# North_Star_Hub_Ver0_3_1.net
KiCad netlist of a schematic drawn in EAGLE
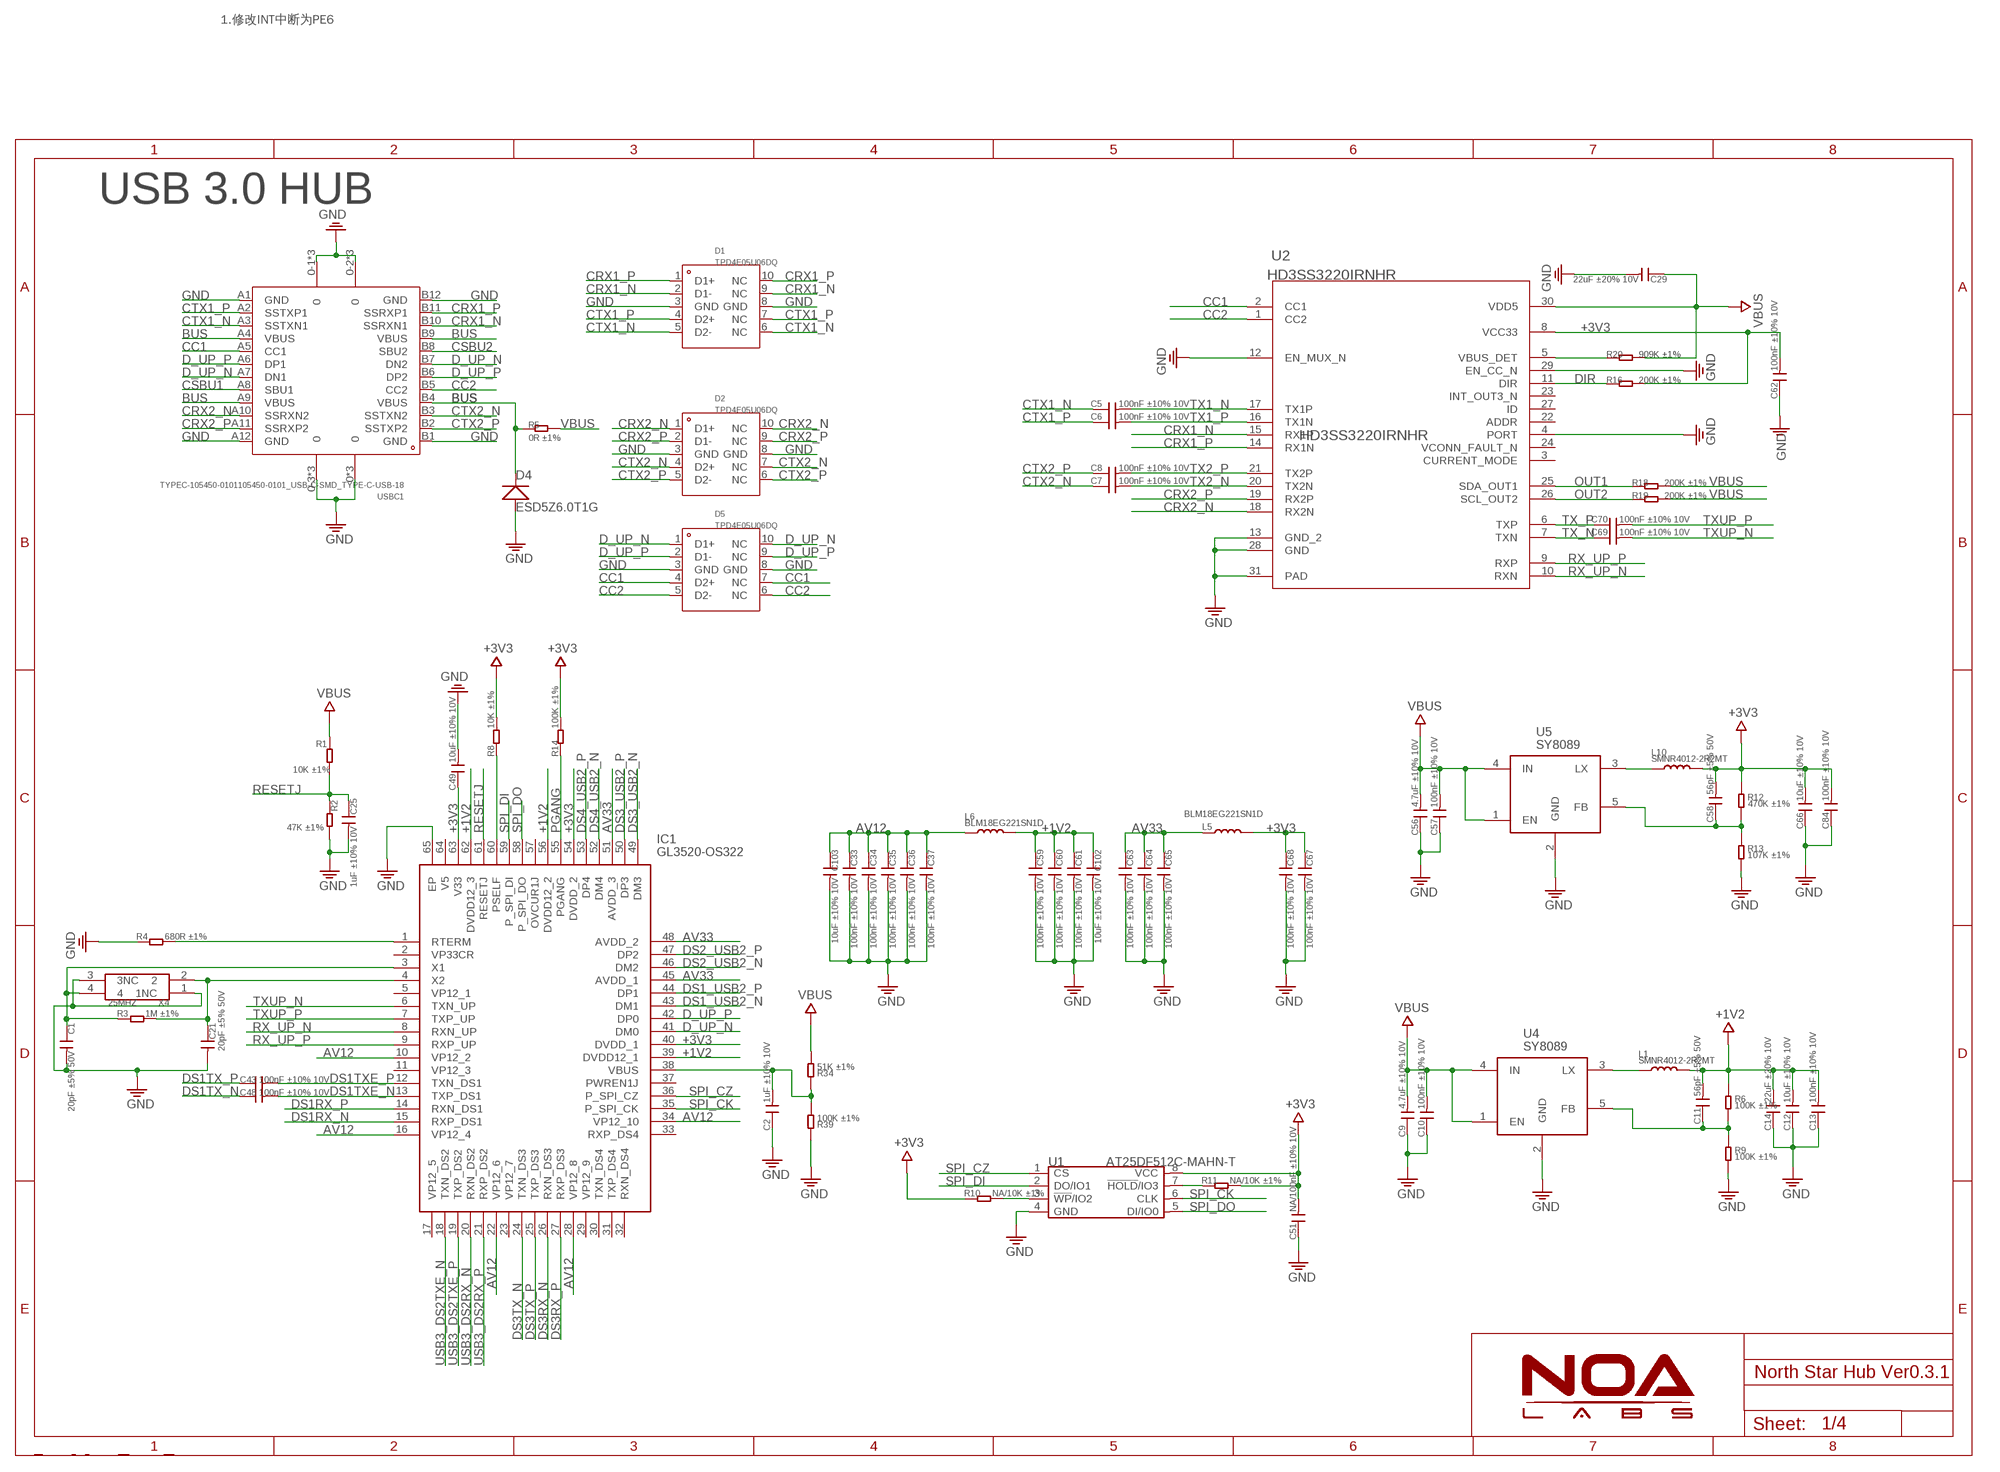
[diagram p0: schematic, sheet 1]
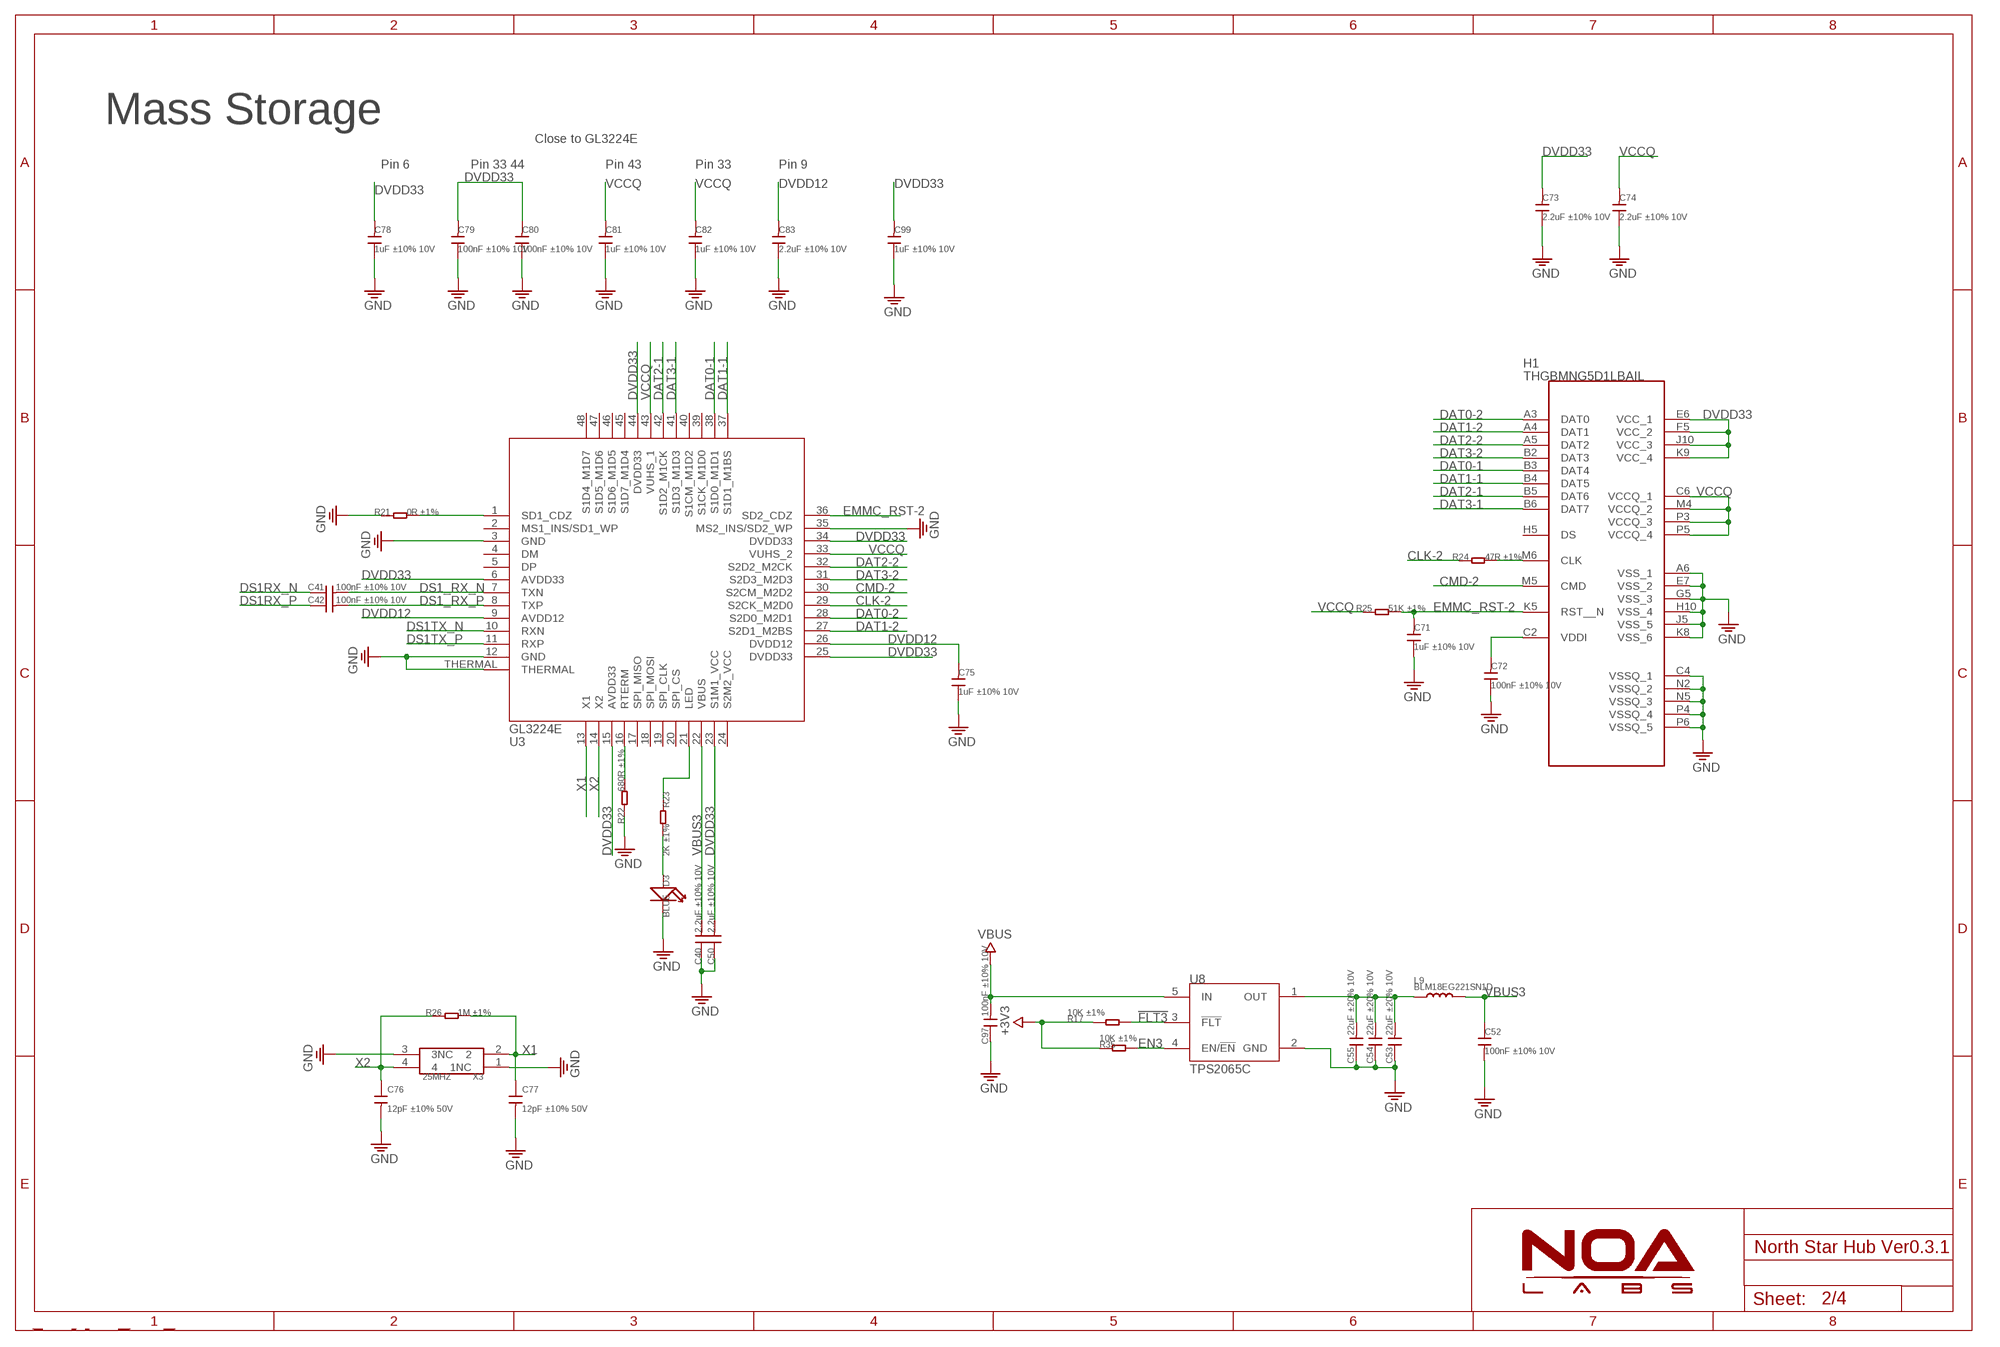
[diagram p1: schematic, sheet 2]
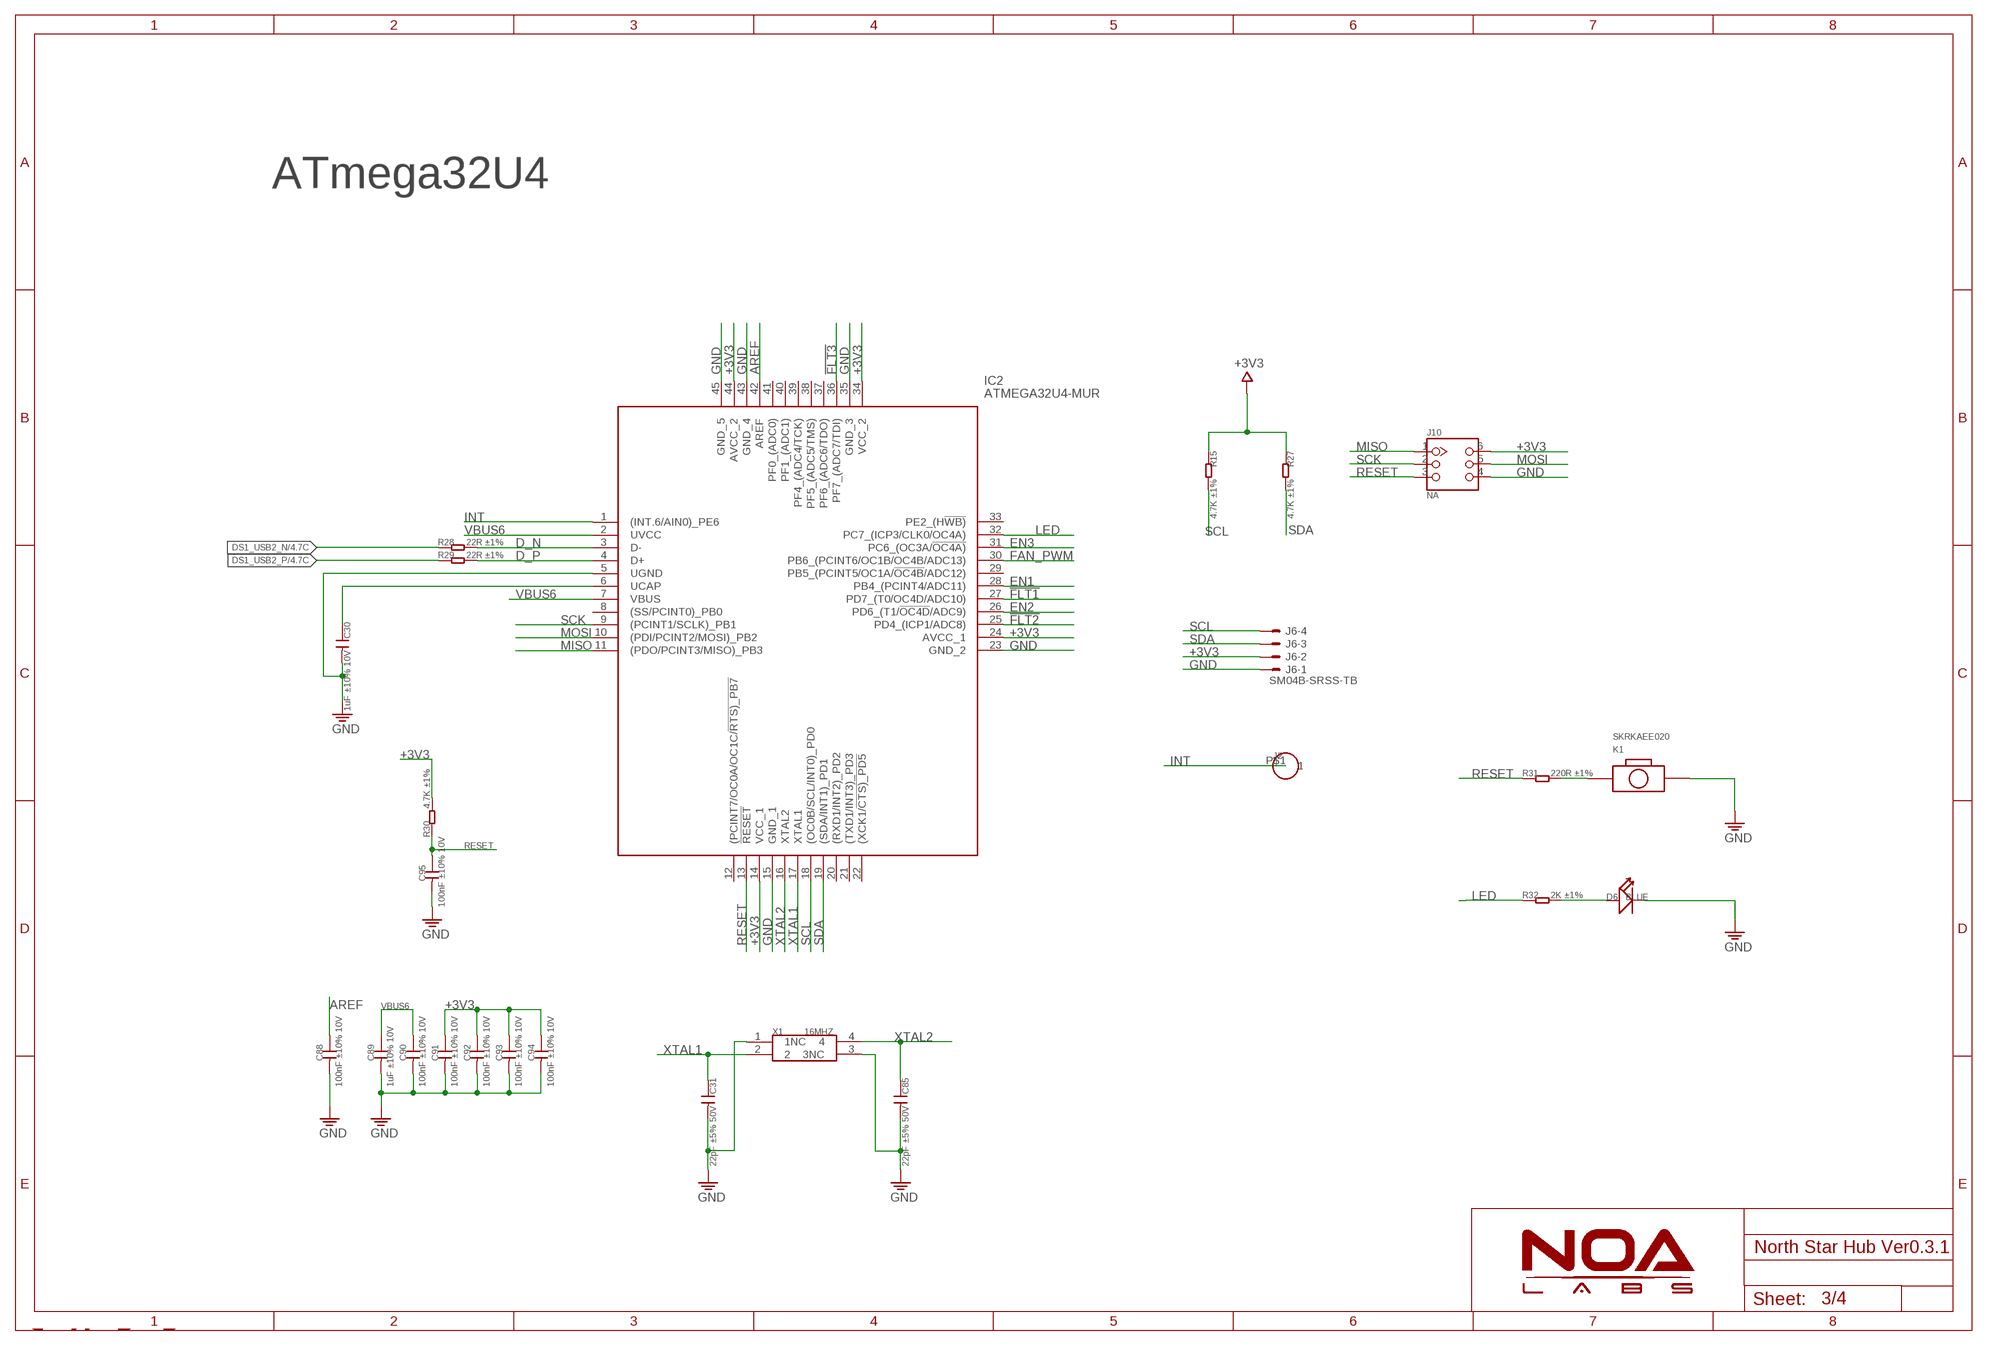
[diagram p2: schematic, sheet 3]
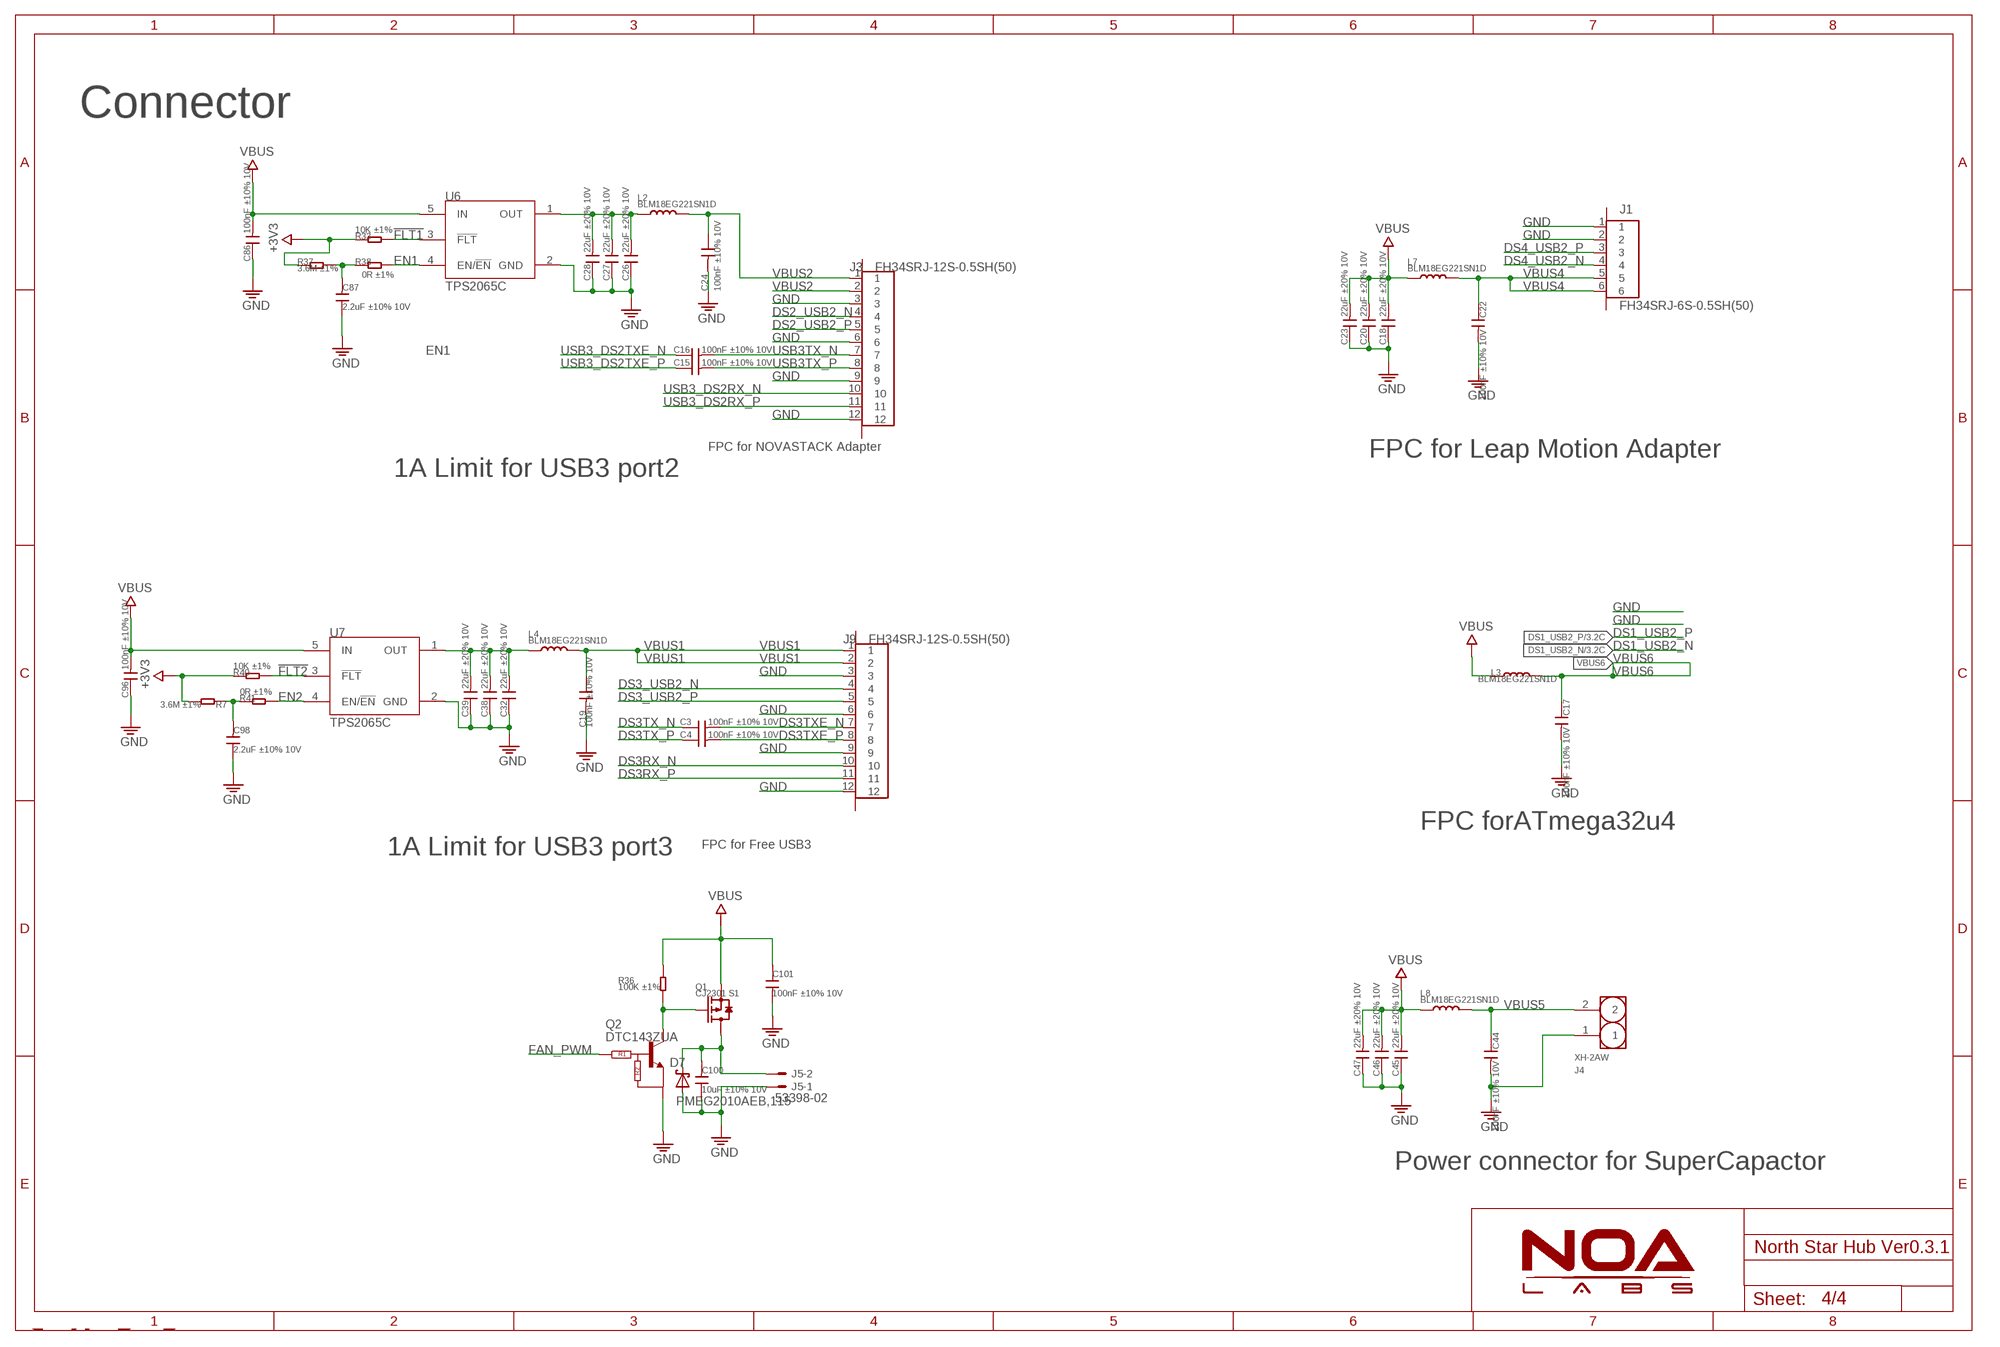
[diagram p3: schematic, sheet 4]

(export (version "E")
  (design (tool "Eeschema 10.0.6"))
  (components
    (comp (ref "C40")
      (value "2.2uF ±10% 10V")
      (footprint "eagle-import:C0402")
      (libsource (lib "eagle-import") (part "C-0402"))
    )
    (comp (ref "C41")
      (value "100nF ±10% 10V")
      (footprint "eagle-import:C0201")
      (libsource (lib "eagle-import") (part "C-0201"))
    )
    (comp (ref "C42")
      (value "100nF ±10% 10V")
      (footprint "eagle-import:C0201")
      (libsource (lib "eagle-import") (part "C-0201"))
    )
    (comp (ref "C50")
      (value "2.2uF ±10% 10V")
      (footprint "eagle-import:C0402")
      (libsource (lib "eagle-import") (part "C-0402"))
    )
    (comp (ref "C52")
      (value "100nF ±10% 10V")
      (footprint "eagle-import:C0402")
      (libsource (lib "eagle-import") (part "C-0402"))
    )
    (comp (ref "C53")
      (value "22uF ±20% 10V")
      (footprint "eagle-import:C0603")
      (libsource (lib "eagle-import") (part "C-0603"))
    )
    (comp (ref "C54")
      (value "22uF ±20% 10V")
      (footprint "eagle-import:C0603")
      (libsource (lib "eagle-import") (part "C-0603"))
    )
    (comp (ref "C55")
      (value "22uF ±20% 10V")
      (footprint "eagle-import:C0603")
      (libsource (lib "eagle-import") (part "C-0603"))
    )
    (comp (ref "C71")
      (value "1uF ±10% 10V")
      (footprint "eagle-import:C0402")
      (libsource (lib "eagle-import") (part "C-0402"))
    )
    (comp (ref "C72")
      (value "100nF ±10% 10V")
      (footprint "eagle-import:C0402")
      (libsource (lib "eagle-import") (part "C-0402"))
    )
    (comp (ref "C73")
      (value "2.2uF ±10% 10V")
      (footprint "eagle-import:C0402")
      (libsource (lib "eagle-import") (part "C-0402"))
    )
    (comp (ref "C74")
      (value "2.2uF ±10% 10V")
      (footprint "eagle-import:C0402")
      (libsource (lib "eagle-import") (part "C-0402"))
    )
    (comp (ref "C75")
      (value "1uF ±10% 10V")
      (footprint "eagle-import:C0402")
      (libsource (lib "eagle-import") (part "C-0402"))
    )
    (comp (ref "C76")
      (value "12pF ±10% 50V")
      (footprint "eagle-import:C0402")
      (libsource (lib "eagle-import") (part "C-0402"))
    )
    (comp (ref "C77")
      (value "12pF ±10% 50V")
      (footprint "eagle-import:C0402")
      (libsource (lib "eagle-import") (part "C-0402"))
    )
    (comp (ref "C78")
      (value "1uF ±10% 10V")
      (footprint "eagle-import:C0402")
      (libsource (lib "eagle-import") (part "C-0402"))
    )
    (comp (ref "C79")
      (value "100nF ±10% 10V")
      (footprint "eagle-import:C0402")
      (libsource (lib "eagle-import") (part "C-0402"))
    )
    (comp (ref "C80")
      (value "100nF ±10% 10V")
      (footprint "eagle-import:C0402")
      (libsource (lib "eagle-import") (part "C-0402"))
    )
    (comp (ref "C81")
      (value "1uF ±10% 10V")
      (footprint "eagle-import:C0402")
      (libsource (lib "eagle-import") (part "C-0402"))
    )
    (comp (ref "C82")
      (value "1uF ±10% 10V")
      (footprint "eagle-import:C0402")
      (libsource (lib "eagle-import") (part "C-0402"))
    )
    (comp (ref "C83")
      (value "2.2uF ±10% 10V")
      (footprint "eagle-import:C0402")
      (libsource (lib "eagle-import") (part "C-0402"))
    )
    (comp (ref "C97")
      (value "100nF ±10% 10V")
      (footprint "eagle-import:C0402")
      (libsource (lib "eagle-import") (part "C-0402"))
    )
    (comp (ref "C99")
      (value "1uF ±10% 10V")
      (footprint "eagle-import:C0402")
      (libsource (lib "eagle-import") (part "C-0402"))
    )
    (comp (ref "D3")
      (value "BLUE")
      (footprint "eagle-import:0402_LED")
      (libsource (lib "eagle-import") (part "LED-0402LED"))
    )
    (comp (ref "H1")
      (value "THGBMNG5D1LBAIL")
      (footprint "eagle-import:BGA153C50P14X14_11.5X13")
      (fields
        (field (name "MANUFACTURER_PART_NUMBER") "IS21ES04G-JCLI-TR")
        (field (name "MOUSER_PART_NUMBER") "870-IS21ES04GJCLITR")
      )
      (libsource (lib "eagle-import") (part "EMMC-SPECIALPAD"))
    )
    (comp (ref "L9")
      (value "BLM18EG221SN1D")
      (footprint "eagle-import:L0603")
      (libsource (lib "eagle-import") (part "L-0603"))
    )
    (comp (ref "R17")
      (value "10K ±1%")
      (footprint "eagle-import:R0402")
      (libsource (lib "eagle-import") (part "R-0402"))
    )
    (comp (ref "R21")
      (value "0R ±1%")
      (footprint "eagle-import:R0402")
      (libsource (lib "eagle-import") (part "R-0402"))
    )
    (comp (ref "R22")
      (value "680R ±1%")
      (footprint "eagle-import:R0402")
      (libsource (lib "eagle-import") (part "R-0402"))
    )
    (comp (ref "R23")
      (value "2K ±1%")
      (footprint "eagle-import:R0402")
      (libsource (lib "eagle-import") (part "R-0402"))
    )
    (comp (ref "R24")
      (value "47R ±1%")
      (footprint "eagle-import:R0402")
      (libsource (lib "eagle-import") (part "R-0402"))
    )
    (comp (ref "R25")
      (value "51K ±1%")
      (footprint "eagle-import:R0402")
      (libsource (lib "eagle-import") (part "R-0402"))
    )
    (comp (ref "R26")
      (value "1M ±1%")
      (footprint "eagle-import:R0402")
      (libsource (lib "eagle-import") (part "R-0402"))
    )
    (comp (ref "R35")
      (value "10K ±1%")
      (footprint "eagle-import:R0402")
      (libsource (lib "eagle-import") (part "R-0402"))
    )
    (comp (ref "U3")
      (value "GL3224E")
      (footprint "eagle-import:TQFN48_7MM")
      (libsource (lib "eagle-import") (part "GL3224E"))
    )
    (comp (ref "U8")
      (value "TPS2065C")
      (footprint "eagle-import:SOT23-5")
      (libsource (lib "eagle-import") (part "TPS20XXC"))
    )
    (comp (ref "X3")
      (value "25MHZ")
      (footprint "eagle-import:4P-SMD-2X1.6MM")
      (libsource (lib "eagle-import") (part "CRYSTAL-XTAL-4P"))
    )
    (comp (ref "C1")
      (value "20pF ±5% 50V")
      (footprint "eagle-import:C0402")
      (libsource (lib "eagle-import") (part "C-0402"))
    )
    (comp (ref "C2")
      (value "1uF ±10% 10V")
      (footprint "eagle-import:C0402")
      (libsource (lib "eagle-import") (part "C-0402"))
    )
    (comp (ref "C5")
      (value "100nF ±10% 10V")
      (footprint "eagle-import:C0201")
      (libsource (lib "eagle-import") (part "C-0201"))
    )
    (comp (ref "C6")
      (value "100nF ±10% 10V")
      (footprint "eagle-import:C0201")
      (libsource (lib "eagle-import") (part "C-0201"))
    )
    (comp (ref "C7")
      (value "100nF ±10% 10V")
      (footprint "eagle-import:C0201")
      (libsource (lib "eagle-import") (part "C-0201"))
    )
    (comp (ref "C8")
      (value "100nF ±10% 10V")
      (footprint "eagle-import:C0201")
      (libsource (lib "eagle-import") (part "C-0201"))
    )
    (comp (ref "C9")
      (value "4.7uF ±10% 10V")
      (footprint "eagle-import:C0603")
      (libsource (lib "eagle-import") (part "C-0603"))
    )
    (comp (ref "C10")
      (value "100nF ±10% 10V")
      (footprint "eagle-import:C0402")
      (libsource (lib "eagle-import") (part "C-0402"))
    )
    (comp (ref "C11")
      (value "56pF ±5% 50V")
      (footprint "eagle-import:C0402")
      (libsource (lib "eagle-import") (part "C-0402"))
    )
    (comp (ref "C12")
      (value "10uF ±10% 10V")
      (footprint "eagle-import:C0603")
      (libsource (lib "eagle-import") (part "C-0603"))
    )
    (comp (ref "C13")
      (value "100nF ±10% 10V")
      (footprint "eagle-import:C0402")
      (libsource (lib "eagle-import") (part "C-0402"))
    )
    (comp (ref "C14")
      (value "22uF ±20% 10V")
      (footprint "eagle-import:C0805")
      (libsource (lib "eagle-import") (part "C-0805"))
    )
    (comp (ref "C21")
      (value "20pF ±5% 50V")
      (footprint "eagle-import:C0402")
      (libsource (lib "eagle-import") (part "C-0402"))
    )
    (comp (ref "C25")
      (value "1uF ±10% 10V")
      (footprint "eagle-import:C0402")
      (libsource (lib "eagle-import") (part "C-0402"))
    )
    (comp (ref "C29")
      (value "22uF ±20% 10V")
      (footprint "eagle-import:C0805")
      (libsource (lib "eagle-import") (part "C-0805"))
    )
    (comp (ref "C33")
      (value "100nF ±10% 10V")
      (footprint "eagle-import:C0402")
      (libsource (lib "eagle-import") (part "C-0402"))
    )
    (comp (ref "C34")
      (value "100nF ±10% 10V")
      (footprint "eagle-import:C0402")
      (libsource (lib "eagle-import") (part "C-0402"))
    )
    (comp (ref "C35")
      (value "100nF ±10% 10V")
      (footprint "eagle-import:C0402")
      (libsource (lib "eagle-import") (part "C-0402"))
    )
    (comp (ref "C36")
      (value "100nF ±10% 10V")
      (footprint "eagle-import:C0402")
      (libsource (lib "eagle-import") (part "C-0402"))
    )
    (comp (ref "C37")
      (value "100nF ±10% 10V")
      (footprint "eagle-import:C0402")
      (libsource (lib "eagle-import") (part "C-0402"))
    )
    (comp (ref "C43")
      (value "100nF ±10% 10V")
      (footprint "eagle-import:C0201")
      (libsource (lib "eagle-import") (part "C-0201"))
    )
    (comp (ref "C48")
      (value "100nF ±10% 10V")
      (footprint "eagle-import:C0201")
      (libsource (lib "eagle-import") (part "C-0201"))
    )
    (comp (ref "C49")
      (value "10uF ±10% 10V")
      (footprint "eagle-import:C0603")
      (libsource (lib "eagle-import") (part "C-0603"))
    )
    (comp (ref "C51")
      (value "NA/100nF ±10% 10V")
      (footprint "eagle-import:C0402")
      (libsource (lib "eagle-import") (part "C-0402"))
    )
    (comp (ref "C56")
      (value "4.7uF ±10% 10V")
      (footprint "eagle-import:C0603")
      (libsource (lib "eagle-import") (part "C-0603"))
    )
    (comp (ref "C57")
      (value "100nF ±10% 10V")
      (footprint "eagle-import:C0402")
      (libsource (lib "eagle-import") (part "C-0402"))
    )
    (comp (ref "C58")
      (value "56pF ±5% 50V")
      (footprint "eagle-import:C0402")
      (libsource (lib "eagle-import") (part "C-0402"))
    )
    (comp (ref "C59")
      (value "100nF ±10% 10V")
      (footprint "eagle-import:C0402")
      (libsource (lib "eagle-import") (part "C-0402"))
    )
    (comp (ref "C60")
      (value "100nF ±10% 10V")
      (footprint "eagle-import:C0402")
      (libsource (lib "eagle-import") (part "C-0402"))
    )
    (comp (ref "C61")
      (value "100nF ±10% 10V")
      (footprint "eagle-import:C0402")
      (libsource (lib "eagle-import") (part "C-0402"))
    )
    (comp (ref "C62")
      (value "100nF ±10% 10V")
      (footprint "eagle-import:C0402")
      (libsource (lib "eagle-import") (part "C-0402"))
    )
    (comp (ref "C63")
      (value "100nF ±10% 10V")
      (footprint "eagle-import:C0402")
      (libsource (lib "eagle-import") (part "C-0402"))
    )
    (comp (ref "C64")
      (value "100nF ±10% 10V")
      (footprint "eagle-import:C0402")
      (libsource (lib "eagle-import") (part "C-0402"))
    )
    (comp (ref "C65")
      (value "100nF ±10% 10V")
      (footprint "eagle-import:C0402")
      (libsource (lib "eagle-import") (part "C-0402"))
    )
    (comp (ref "C66")
      (value "10uF ±10% 10V")
      (footprint "eagle-import:C0603")
      (libsource (lib "eagle-import") (part "C-0603"))
    )
    (comp (ref "C67")
      (value "100nF ±10% 10V")
      (footprint "eagle-import:C0402")
      (libsource (lib "eagle-import") (part "C-0402"))
    )
    (comp (ref "C68")
      (value "100nF ±10% 10V")
      (footprint "eagle-import:C0402")
      (libsource (lib "eagle-import") (part "C-0402"))
    )
    (comp (ref "C69")
      (value "100nF ±10% 10V")
      (footprint "eagle-import:C0201")
      (libsource (lib "eagle-import") (part "C-0201"))
    )
    (comp (ref "C70")
      (value "100nF ±10% 10V")
      (footprint "eagle-import:C0201")
      (libsource (lib "eagle-import") (part "C-0201"))
    )
    (comp (ref "C84")
      (value "100nF ±10% 10V")
      (footprint "eagle-import:C0402")
      (libsource (lib "eagle-import") (part "C-0402"))
    )
    (comp (ref "C102")
      (value "10uF ±10% 10V")
      (footprint "eagle-import:C0603")
      (libsource (lib "eagle-import") (part "C-0603"))
    )
    (comp (ref "C103")
      (value "10uF ±10% 10V")
      (footprint "eagle-import:C0603")
      (libsource (lib "eagle-import") (part "C-0603"))
    )
    (comp (ref "D1")
      (value "TPD4E05U06DQ")
      (footprint "eagle-import:USON-10_L2.5-W1.0-P0.50-BL")
      (fields
        (field (name "BOM_MANUFACTURER_PART") "TPD4E05U06DQAR")
        (field (name "BOM_SUPPLIER_PART") "C138714")
        (field (name "CONTRIBUTOR") "LCSC")
      )
      (libsource (lib "eagle-import") (part "TPD4E05U06DQARTPD4E05U06DQAR_C138714_USON-10_L2.5-W1.0-P0.50-BL"))
    )
    (comp (ref "D2")
      (value "TPD4E05U06DQ")
      (footprint "eagle-import:USON-10_L2.5-W1.0-P0.50-BL")
      (fields
        (field (name "BOM_MANUFACTURER_PART") "TPD4E05U06DQAR")
        (field (name "BOM_SUPPLIER_PART") "C138714")
        (field (name "CONTRIBUTOR") "LCSC")
      )
      (libsource (lib "eagle-import") (part "TPD4E05U06DQARTPD4E05U06DQAR_C138714_USON-10_L2.5-W1.0-P0.50-BL"))
    )
    (comp (ref "D4")
      (value "ESD5Z6.0T1G")
      (footprint "eagle-import:SOD523")
      (libsource (lib "eagle-import") (part "D-0603"))
    )
    (comp (ref "D5")
      (value "TPD4E05U06DQ")
      (footprint "eagle-import:USON-10_L2.5-W1.0-P0.50-BL")
      (fields
        (field (name "BOM_MANUFACTURER_PART") "TPD4E05U06DQAR")
        (field (name "BOM_SUPPLIER_PART") "C138714")
        (field (name "CONTRIBUTOR") "LCSC")
      )
      (libsource (lib "eagle-import") (part "TPD4E05U06DQARTPD4E05U06DQAR_C138714_USON-10_L2.5-W1.0-P0.50-BL"))
    )
    (comp (ref "IC1")
      (value "GL3520-OS322")
      (footprint "eagle-import:QFN40P800X800X80-65N")
      (fields (field (name "MANUFACTURER_PART_NUMBER") "GL3520 64"))
      (libsource (lib "eagle-import") (part "GL3520_64"))
    )
    (comp (ref "L1")
      (value "SMNR4012-2R2MT")
      (footprint "eagle-import:L4012")
      (libsource (lib "eagle-import") (part "L-4012"))
    )
    (comp (ref "L5")
      (value "BLM18EG221SN1D")
      (footprint "eagle-import:L0603")
      (libsource (lib "eagle-import") (part "L-0603"))
    )
    (comp (ref "L6")
      (value "BLM18EG221SN1D")
      (footprint "eagle-import:L0603")
      (libsource (lib "eagle-import") (part "L-0603"))
    )
    (comp (ref "L10")
      (value "SMNR4012-2R2MT")
      (footprint "eagle-import:L4012")
      (libsource (lib "eagle-import") (part "L-4012"))
    )
    (comp (ref "R1")
      (value "10K ±1%")
      (footprint "eagle-import:R0402")
      (libsource (lib "eagle-import") (part "R-0402"))
    )
    (comp (ref "R2")
      (value "47K ±1%")
      (footprint "eagle-import:R0402")
      (libsource (lib "eagle-import") (part "R-0402"))
    )
    (comp (ref "R3")
      (value "1M ±1%")
      (footprint "eagle-import:R0402")
      (libsource (lib "eagle-import") (part "R-0402"))
    )
    (comp (ref "R4")
      (value "680R ±1%")
      (footprint "eagle-import:R0402")
      (libsource (lib "eagle-import") (part "R-0402"))
    )
    (comp (ref "R5")
      (value "0R ±1%")
      (footprint "eagle-import:R0805")
      (libsource (lib "eagle-import") (part "R-0805"))
    )
    (comp (ref "R6")
      (value "100K ±1%")
      (footprint "eagle-import:R0402")
      (libsource (lib "eagle-import") (part "R-0402"))
    )
    (comp (ref "R8")
      (value "10K ±1%")
      (footprint "eagle-import:R0402")
      (libsource (lib "eagle-import") (part "R-0402"))
    )
    (comp (ref "R9")
      (value "100K ±1%")
      (footprint "eagle-import:R0402")
      (libsource (lib "eagle-import") (part "R-0402"))
    )
    (comp (ref "R10")
      (value "NA/10K ±1%")
      (footprint "eagle-import:R0402")
      (libsource (lib "eagle-import") (part "R-0402"))
    )
    (comp (ref "R11")
      (value "NA/10K ±1%")
      (footprint "eagle-import:R0402")
      (libsource (lib "eagle-import") (part "R-0402"))
    )
    (comp (ref "R12")
      (value "470K ±1%")
      (footprint "eagle-import:R0402")
      (libsource (lib "eagle-import") (part "R-0402"))
    )
    (comp (ref "R13")
      (value "107K ±1%")
      (footprint "eagle-import:R0402")
      (libsource (lib "eagle-import") (part "R-0402"))
    )
    (comp (ref "R14")
      (value "100K ±1%")
      (footprint "eagle-import:R0402")
      (libsource (lib "eagle-import") (part "R-0402"))
    )
    (comp (ref "R16")
      (value "200K ±1%")
      (footprint "eagle-import:R0402")
      (libsource (lib "eagle-import") (part "R-0402"))
    )
    (comp (ref "R18")
      (value "200K ±1%")
      (footprint "eagle-import:R0402")
      (libsource (lib "eagle-import") (part "R-0402"))
    )
    (comp (ref "R19")
      (value "200K ±1%")
      (footprint "eagle-import:R0402")
      (libsource (lib "eagle-import") (part "R-0402"))
    )
    (comp (ref "R20")
      (value "909K ±1%")
      (footprint "eagle-import:R0402")
      (libsource (lib "eagle-import") (part "R-0402"))
    )
    (comp (ref "R34")
      (value "51K ±1%")
      (footprint "eagle-import:R0402")
      (libsource (lib "eagle-import") (part "R-0402"))
    )
    (comp (ref "R39")
      (value "100K ±1%")
      (footprint "eagle-import:R0402")
      (libsource (lib "eagle-import") (part "R-0402"))
    )
    (comp (ref "U1")
      (value "AT25DF512C-MAHN-T")
      (footprint "eagle-import:SOIC8-6.0")
      (libsource (lib "eagle-import") (part "W25Q"))
    )
    (comp (ref "U2")
      (value "HD3SS3220IRNHR")
      (footprint "eagle-import:RNH0030A")
      (fields (field (name "MANUFACTURER") "Texas Instruments"))
      (libsource (lib "eagle-import") (part "HD3SS3220IRNHR"))
    )
    (comp (ref "U4")
      (value "SY8089")
      (footprint "eagle-import:SOT23-5")
      (libsource (lib "eagle-import") (part "SY8089"))
    )
    (comp (ref "U5")
      (value "SY8089")
      (footprint "eagle-import:SOT23-5")
      (libsource (lib "eagle-import") (part "SY8089"))
    )
    (comp (ref "USBC1")
      (value "TYPEC-105450-0101105450-0101_USB-C-SMD_TYPE-C-USB-18")
      (footprint "eagle-import:USB-C-SMD_TYPE-C-USB-18")
      (fields
        (field (name "BOM_MANUFACTURER_PART") "105450-0101")
        (field (name "BOM_SUPPLIER_PART") "C134092")
        (field (name "CONTRIBUTOR") "LCSC")
      )
      (libsource (lib "eagle-import") (part "TYPEC-105450-0101105450-0101_USB-C-SMD_TYPE-C-USB-18"))
    )
    (comp (ref "X4")
      (value "25MHZ")
      (footprint "eagle-import:4P-SMD-2X1.6MM")
      (libsource (lib "eagle-import") (part "CRYSTAL-XTAL-4P"))
    )
    (comp (ref "C3")
      (value "100nF ±10% 10V")
      (footprint "eagle-import:C0201")
      (libsource (lib "eagle-import") (part "C-0201"))
    )
    (comp (ref "C4")
      (value "100nF ±10% 10V")
      (footprint "eagle-import:C0201")
      (libsource (lib "eagle-import") (part "C-0201"))
    )
    (comp (ref "C15")
      (value "100nF ±10% 10V")
      (footprint "eagle-import:C0201")
      (libsource (lib "eagle-import") (part "C-0201"))
    )
    (comp (ref "C16")
      (value "100nF ±10% 10V")
      (footprint "eagle-import:C0201")
      (libsource (lib "eagle-import") (part "C-0201"))
    )
    (comp (ref "C17")
      (value "100nF ±10% 10V")
      (footprint "eagle-import:C0402")
      (libsource (lib "eagle-import") (part "C-0402"))
    )
    (comp (ref "C18")
      (value "22uF ±20% 10V")
      (footprint "eagle-import:C0603")
      (libsource (lib "eagle-import") (part "C-0603"))
    )
    (comp (ref "C19")
      (value "100nF ±10% 10V")
      (footprint "eagle-import:C0402")
      (libsource (lib "eagle-import") (part "C-0402"))
    )
    (comp (ref "C20")
      (value "22uF ±20% 10V")
      (footprint "eagle-import:C0603")
      (libsource (lib "eagle-import") (part "C-0603"))
    )
    (comp (ref "C22")
      (value "100nF ±10% 10V")
      (footprint "eagle-import:C0402")
      (libsource (lib "eagle-import") (part "C-0402"))
    )
    (comp (ref "C23")
      (value "22uF ±20% 10V")
      (footprint "eagle-import:C0603")
      (libsource (lib "eagle-import") (part "C-0603"))
    )
    (comp (ref "C24")
      (value "100nF ±10% 10V")
      (footprint "eagle-import:C0402")
      (libsource (lib "eagle-import") (part "C-0402"))
    )
    (comp (ref "C26")
      (value "22uF ±20% 10V")
      (footprint "eagle-import:C0603")
      (libsource (lib "eagle-import") (part "C-0603"))
    )
    (comp (ref "C27")
      (value "22uF ±20% 10V")
      (footprint "eagle-import:C0603")
      (libsource (lib "eagle-import") (part "C-0603"))
    )
    (comp (ref "C28")
      (value "22uF ±20% 10V")
      (footprint "eagle-import:C0603")
      (libsource (lib "eagle-import") (part "C-0603"))
    )
    (comp (ref "C32")
      (value "22uF ±20% 10V")
      (footprint "eagle-import:C0603")
      (libsource (lib "eagle-import") (part "C-0603"))
    )
    (comp (ref "C38")
      (value "22uF ±20% 10V")
      (footprint "eagle-import:C0603")
      (libsource (lib "eagle-import") (part "C-0603"))
    )
    (comp (ref "C39")
      (value "22uF ±20% 10V")
      (footprint "eagle-import:C0603")
      (libsource (lib "eagle-import") (part "C-0603"))
    )
    (comp (ref "C44")
      (value "100nF ±10% 10V")
      (footprint "eagle-import:C0402")
      (libsource (lib "eagle-import") (part "C-0402"))
    )
    (comp (ref "C45")
      (value "22uF ±20% 10V")
      (footprint "eagle-import:C0603")
      (libsource (lib "eagle-import") (part "C-0603"))
    )
    (comp (ref "C46")
      (value "22uF ±20% 10V")
      (footprint "eagle-import:C0603")
      (libsource (lib "eagle-import") (part "C-0603"))
    )
    (comp (ref "C47")
      (value "22uF ±20% 10V")
      (footprint "eagle-import:C0603")
      (libsource (lib "eagle-import") (part "C-0603"))
    )
    (comp (ref "C86")
      (value "100nF ±10% 10V")
      (footprint "eagle-import:C0402")
      (libsource (lib "eagle-import") (part "C-0402"))
    )
    (comp (ref "C87")
      (value "2.2uF ±10% 10V")
      (footprint "eagle-import:C0402")
      (libsource (lib "eagle-import") (part "C-0402"))
    )
    (comp (ref "C96")
      (value "100nF ±10% 10V")
      (footprint "eagle-import:C0402")
      (libsource (lib "eagle-import") (part "C-0402"))
    )
    (comp (ref "C98")
      (value "2.2uF ±10% 10V")
      (footprint "eagle-import:C0402")
      (libsource (lib "eagle-import") (part "C-0402"))
    )
    (comp (ref "C100")
      (value "10uF ±10% 10V")
      (footprint "eagle-import:C0603")
      (libsource (lib "eagle-import") (part "C-0603"))
    )
    (comp (ref "C101")
      (value "100nF ±10% 10V")
      (footprint "eagle-import:C0402")
      (libsource (lib "eagle-import") (part "C-0402"))
    )
    (comp (ref "D7")
      (value "PMEG2010AEB,115")
      (footprint "eagle-import:SOD323")
      (libsource (lib "eagle-import") (part "SCHOTTKY-SOD323"))
    )
    (comp (ref "J1")
      (value "FH34SRJ-6S-0.5SH(50)")
      (footprint "eagle-import:FH34RJ-6S")
      (libsource (lib "eagle-import") (part "FPC-0.5-6P-FH34RJ"))
    )
    (comp (ref "J3")
      (value "FH34SRJ-12S-0.5SH(50)")
      (footprint "eagle-import:FPC-0.5-12P")
      (libsource (lib "eagle-import") (part "FPC-0.5-12PFPC-0.5-12P"))
    )
    (comp (ref "J4")
      (value "XH-2AW")
      (footprint "eagle-import:XH-02-90")
      (libsource (lib "eagle-import") (part "HEADER-2P-90DEG-FEMALE"))
    )
    (comp (ref "J5")
      (value "53398-02")
      (footprint "eagle-import:53398-02")
      (fields (field (name "MF") "MOLEX"))
      (libsource (lib "eagle-import") (part "53?-02398"))
    )
    (comp (ref "J9")
      (value "FH34SRJ-12S-0.5SH(50)")
      (footprint "eagle-import:FPC-0.5-12P")
      (libsource (lib "eagle-import") (part "FPC-0.5-12PFPC-0.5-12P"))
    )
    (comp (ref "L2")
      (value "BLM18EG221SN1D")
      (footprint "eagle-import:L0603")
      (libsource (lib "eagle-import") (part "L-0603"))
    )
    (comp (ref "L3")
      (value "BLM18EG221SN1D")
      (footprint "eagle-import:L0603")
      (libsource (lib "eagle-import") (part "L-0603"))
    )
    (comp (ref "L4")
      (value "BLM18EG221SN1D")
      (footprint "eagle-import:L0603")
      (libsource (lib "eagle-import") (part "L-0603"))
    )
    (comp (ref "L7")
      (value "BLM18EG221SN1D")
      (footprint "eagle-import:L0603")
      (libsource (lib "eagle-import") (part "L-0603"))
    )
    (comp (ref "L8")
      (value "BLM18EG221SN1D")
      (footprint "eagle-import:L0603")
      (libsource (lib "eagle-import") (part "L-0603"))
    )
    (comp (ref "Q1")
      (value "CJ2301 S1")
      (footprint "eagle-import:SOT23")
      (libsource (lib "eagle-import") (part "MOSFET-P-SOT23"))
    )
    (comp (ref "Q2")
      (value "DTC143ZUA")
      (footprint "eagle-import:SOT323")
      (libsource (lib "eagle-import") (part "DIGITAL-NPNUE"))
    )
    (comp (ref "R7")
      (value "3.6M ±1%")
      (footprint "eagle-import:R0402")
      (libsource (lib "eagle-import") (part "R-0402"))
    )
    (comp (ref "R33")
      (value "10K ±1%")
      (footprint "eagle-import:R0402")
      (libsource (lib "eagle-import") (part "R-0402"))
    )
    (comp (ref "R36")
      (value "100K ±1%")
      (footprint "eagle-import:R0402")
      (libsource (lib "eagle-import") (part "R-0402"))
    )
    (comp (ref "R37")
      (value "3.6M ±1%")
      (footprint "eagle-import:R0402")
      (libsource (lib "eagle-import") (part "R-0402"))
    )
    (comp (ref "R38")
      (value "0R ±1%")
      (footprint "eagle-import:R0402")
      (libsource (lib "eagle-import") (part "R-0402"))
    )
    (comp (ref "R40")
      (value "10K ±1%")
      (footprint "eagle-import:R0402")
      (libsource (lib "eagle-import") (part "R-0402"))
    )
    (comp (ref "R41")
      (value "0R ±1%")
      (footprint "eagle-import:R0402")
      (libsource (lib "eagle-import") (part "R-0402"))
    )
    (comp (ref "U6")
      (value "TPS2065C")
      (footprint "eagle-import:SOT23-5")
      (libsource (lib "eagle-import") (part "TPS20XXC"))
    )
    (comp (ref "U7")
      (value "TPS2065C")
      (footprint "eagle-import:SOT23-5")
      (libsource (lib "eagle-import") (part "TPS20XXC"))
    )
    (comp (ref "C30")
      (value "1uF ±10% 10V")
      (footprint "eagle-import:C0402")
      (libsource (lib "eagle-import") (part "C-0402"))
    )
    (comp (ref "C31")
      (value "22pF ±5% 50V")
      (footprint "eagle-import:C0402")
      (libsource (lib "eagle-import") (part "C-0402"))
    )
    (comp (ref "C85")
      (value "22pF ±5% 50V")
      (footprint "eagle-import:C0402")
      (libsource (lib "eagle-import") (part "C-0402"))
    )
    (comp (ref "C88")
      (value "100nF ±10% 10V")
      (footprint "eagle-import:C0402")
      (libsource (lib "eagle-import") (part "C-0402"))
    )
    (comp (ref "C89")
      (value "1uF ±10% 10V")
      (footprint "eagle-import:C0402")
      (libsource (lib "eagle-import") (part "C-0402"))
    )
    (comp (ref "C90")
      (value "100nF ±10% 10V")
      (footprint "eagle-import:C0402")
      (libsource (lib "eagle-import") (part "C-0402"))
    )
    (comp (ref "C91")
      (value "100nF ±10% 10V")
      (footprint "eagle-import:C0402")
      (libsource (lib "eagle-import") (part "C-0402"))
    )
    (comp (ref "C92")
      (value "100nF ±10% 10V")
      (footprint "eagle-import:C0402")
      (libsource (lib "eagle-import") (part "C-0402"))
    )
    (comp (ref "C93")
      (value "100nF ±10% 10V")
      (footprint "eagle-import:C0402")
      (libsource (lib "eagle-import") (part "C-0402"))
    )
    (comp (ref "C94")
      (value "100nF ±10% 10V")
      (footprint "eagle-import:C0402")
      (libsource (lib "eagle-import") (part "C-0402"))
    )
    (comp (ref "C95")
      (value "100nF ±10% 10V")
      (footprint "eagle-import:C0402")
      (libsource (lib "eagle-import") (part "C-0402"))
    )
    (comp (ref "D6")
      (value "BLUE")
      (footprint "eagle-import:0402_LED")
      (libsource (lib "eagle-import") (part "LED-0402LED"))
    )
    (comp (ref "IC2")
      (value "ATMEGA32U4-MUR")
      (footprint "eagle-import:QFN50P700X700X100-45N")
      (fields
        (field (name "MANUFACTURER_PART_NUMBER") "ATMEGA32U4-MU")
        (field (name "MOUSER_PART_NUMBER") "556-ATMEGA32U4-MU")
        (field (name "RS_PART_NUMBER") "1310290P")
      )
      (libsource (lib "eagle-import") (part "ATMEGA32U4-MU"))
    )
    (comp (ref "J2")
      (value "HEADER-1P-32")
      (footprint "eagle-import:1P-60_32MIL")
      (libsource (lib "eagle-import") (part "HEADER-1P-32"))
    )
    (comp (ref "J6")
      (value "SM04B-SRSS-TB")
      (footprint "eagle-import:SM04B-SRSS-TB")
      (libsource (lib "eagle-import") (part "?M04B-SRSS-TBS"))
    )
    (comp (ref "J10")
      (value "NA")
      (footprint "eagle-import:2X3P-2.54-65_35MIL")
      (libsource (lib "eagle-import") (part "HEADER-2X3P-THT"))
    )
    (comp (ref "K1")
      (value "SKRKAEE020")
      (footprint "eagle-import:SKRKAEE020")
      (libsource (lib "eagle-import") (part "BUTTON-2PSKRKAEE020"))
    )
    (comp (ref "R15")
      (value "4.7K ±1%")
      (footprint "eagle-import:R0402")
      (libsource (lib "eagle-import") (part "R-0402"))
    )
    (comp (ref "R27")
      (value "4.7K ±1%")
      (footprint "eagle-import:R0402")
      (libsource (lib "eagle-import") (part "R-0402"))
    )
    (comp (ref "R28")
      (value "22R ±1%")
      (footprint "eagle-import:R0402")
      (libsource (lib "eagle-import") (part "R-0402"))
    )
    (comp (ref "R29")
      (value "22R ±1%")
      (footprint "eagle-import:R0402")
      (libsource (lib "eagle-import") (part "R-0402"))
    )
    (comp (ref "R30")
      (value "4.7K ±1%")
      (footprint "eagle-import:R0402")
      (libsource (lib "eagle-import") (part "R-0402"))
    )
    (comp (ref "R31")
      (value "220R ±1%")
      (footprint "eagle-import:R0402")
      (libsource (lib "eagle-import") (part "R-0402"))
    )
    (comp (ref "R32")
      (value "2K ±1%")
      (footprint "eagle-import:R0402")
      (libsource (lib "eagle-import") (part "R-0402"))
    )
    (comp (ref "X1")
      (value "16MHZ")
      (footprint "eagle-import:4P-SMD-3.2X2.5")
      (libsource (lib "eagle-import") (part "CRYSTAL-XTAL-4P-3225"))
    )
  )
  (nets
    (net (code "1") (name "+1V2") (class "Default")
      (node (ref "C102") (pin "1") (pinfunction "1_1") (pintype "passive"))
      (node (ref "C11") (pin "2") (pinfunction "2_2") (pintype "passive"))
      (node (ref "C12") (pin "2") (pinfunction "2_2") (pintype "passive"))
      (node (ref "C13") (pin "2") (pinfunction "2_2") (pintype "passive"))
      (node (ref "C14") (pin "2") (pinfunction "2_2") (pintype "passive"))
      (node (ref "C59") (pin "1") (pinfunction "1_1") (pintype "passive"))
      (node (ref "C60") (pin "1") (pinfunction "1_1") (pintype "passive"))
      (node (ref "C61") (pin "1") (pinfunction "1_1") (pintype "passive"))
      (node (ref "IC1") (pin "39") (pinfunction "DVDD12_1_39") (pintype "bidirectional"))
      (node (ref "IC1") (pin "56") (pinfunction "DVDD12_2_56") (pintype "bidirectional"))
      (node (ref "IC1") (pin "62") (pinfunction "DVDD12_3_62") (pintype "bidirectional"))
      (node (ref "L1") (pin "2") (pinfunction "2_2") (pintype "passive"))
      (node (ref "L6") (pin "2") (pinfunction "2_2") (pintype "passive"))
      (node (ref "R6") (pin "1") (pinfunction "1_1") (pintype "passive"))
    )
    (net (code "2") (name "+3V3") (class "Default")
      (node (ref "C49") (pin "1") (pinfunction "1_1") (pintype "passive"))
      (node (ref "C51") (pin "2") (pinfunction "2_2") (pintype "passive"))
      (node (ref "C58") (pin "2") (pinfunction "2_2") (pintype "passive"))
      (node (ref "C62") (pin "2") (pinfunction "2_2") (pintype "passive"))
      (node (ref "C66") (pin "2") (pinfunction "2_2") (pintype "passive"))
      (node (ref "C67") (pin "1") (pinfunction "1_1") (pintype "passive"))
      (node (ref "C68") (pin "1") (pinfunction "1_1") (pintype "passive"))
      (node (ref "C84") (pin "2") (pinfunction "2_2") (pintype "passive"))
      (node (ref "C91") (pin "1") (pinfunction "1_1") (pintype "passive"))
      (node (ref "C92") (pin "1") (pinfunction "1_1") (pintype "passive"))
      (node (ref "C93") (pin "1") (pinfunction "1_1") (pintype "passive"))
      (node (ref "C94") (pin "1") (pinfunction "1_1") (pintype "passive"))
      (node (ref "IC1") (pin "40") (pinfunction "DVDD_1_40") (pintype "bidirectional"))
      (node (ref "IC1") (pin "54") (pinfunction "DVDD_2_54") (pintype "bidirectional"))
      (node (ref "IC1") (pin "63") (pinfunction "V33_63") (pintype "bidirectional"))
      (node (ref "IC2") (pin "14") (pinfunction "VCC_1_14") (pintype "bidirectional"))
      (node (ref "IC2") (pin "24") (pinfunction "AVCC_1_24") (pintype "bidirectional"))
      (node (ref "IC2") (pin "34") (pinfunction "VCC_2_34") (pintype "bidirectional"))
      (node (ref "IC2") (pin "44") (pinfunction "AVCC_2_44") (pintype "bidirectional"))
      (node (ref "J10") (pin "6") (pinfunction "6_6") (pintype "bidirectional"))
      (node (ref "J6") (pin "2") (pinfunction "S_2") (pintype "passive"))
      (node (ref "L10") (pin "2") (pinfunction "2_2") (pintype "passive"))
      (node (ref "L5") (pin "2") (pinfunction "2_2") (pintype "passive"))
      (node (ref "R10") (pin "1") (pinfunction "1_1") (pintype "passive"))
      (node (ref "R11") (pin "2") (pinfunction "2_2") (pintype "passive"))
      (node (ref "R12") (pin "1") (pinfunction "1_1") (pintype "passive"))
      (node (ref "R14") (pin "2") (pinfunction "2_2") (pintype "passive"))
      (node (ref "R15") (pin "1") (pinfunction "1_1") (pintype "passive"))
      (node (ref "R16") (pin "2") (pinfunction "2_2") (pintype "passive"))
      (node (ref "R17") (pin "1") (pinfunction "1_1") (pintype "passive"))
      (node (ref "R27") (pin "1") (pinfunction "1_1") (pintype "passive"))
      (node (ref "R30") (pin "2") (pinfunction "2_2") (pintype "passive"))
      (node (ref "R33") (pin "1") (pinfunction "1_1") (pintype "passive"))
      (node (ref "R35") (pin "1") (pinfunction "1_1") (pintype "passive"))
      (node (ref "R37") (pin "2") (pinfunction "2_2") (pintype "passive"))
      (node (ref "R40") (pin "1") (pinfunction "1_1") (pintype "passive"))
      (node (ref "R7") (pin "1") (pinfunction "1_1") (pintype "passive"))
      (node (ref "R8") (pin "2") (pinfunction "2_2") (pintype "passive"))
      (node (ref "U1") (pin "8") (pinfunction "VCC_8") (pintype "bidirectional"))
      (node (ref "U2") (pin "8") (pinfunction "VCC33_8") (pintype "power_in"))
    )
    (net (code "3") (name "AREF") (class "Default")
      (node (ref "C88") (pin "1") (pinfunction "1_1") (pintype "passive"))
      (node (ref "IC2") (pin "42") (pinfunction "AREF_42") (pintype "bidirectional"))
    )
    (net (code "4") (name "AV12") (class "Default")
      (node (ref "C103") (pin "1") (pinfunction "1_1") (pintype "passive"))
      (node (ref "C33") (pin "1") (pinfunction "1_1") (pintype "passive"))
      (node (ref "C34") (pin "1") (pinfunction "1_1") (pintype "passive"))
      (node (ref "C35") (pin "1") (pinfunction "1_1") (pintype "passive"))
      (node (ref "C36") (pin "1") (pinfunction "1_1") (pintype "passive"))
      (node (ref "C37") (pin "1") (pinfunction "1_1") (pintype "passive"))
      (node (ref "IC1") (pin "10") (pinfunction "VP12_2_10") (pintype "bidirectional"))
      (node (ref "IC1") (pin "16") (pinfunction "VP12_4_16") (pintype "bidirectional"))
      (node (ref "IC1") (pin "22") (pinfunction "VP12_6_22") (pintype "bidirectional"))
      (node (ref "IC1") (pin "28") (pinfunction "VP12_8_28") (pintype "bidirectional"))
      (node (ref "IC1") (pin "34") (pinfunction "VP12_10_34") (pintype "bidirectional"))
      (node (ref "L6") (pin "1") (pinfunction "1_1") (pintype "passive"))
    )
    (net (code "5") (name "AV33") (class "Default")
      (node (ref "C63") (pin "1") (pinfunction "1_1") (pintype "passive"))
      (node (ref "C64") (pin "1") (pinfunction "1_1") (pintype "passive"))
      (node (ref "C65") (pin "1") (pinfunction "1_1") (pintype "passive"))
      (node (ref "IC1") (pin "45") (pinfunction "AVDD_1_45") (pintype "bidirectional"))
      (node (ref "IC1") (pin "48") (pinfunction "AVDD_2_48") (pintype "bidirectional"))
      (node (ref "IC1") (pin "51") (pinfunction "AVDD_3_51") (pintype "bidirectional"))
      (node (ref "L5") (pin "1") (pinfunction "1_1") (pintype "passive"))
    )
    (net (code "6") (name "BUS") (class "Default")
      (node (ref "D4") (pin "-") (pinfunction "-_-") (pintype "passive"))
      (node (ref "R5") (pin "1") (pinfunction "1_1") (pintype "passive"))
      (node (ref "USBC1") (pin "A4") (pinfunction "VBUS_A4") (pintype "passive"))
      (node (ref "USBC1") (pin "A9") (pinfunction "VBUS_A9") (pintype "passive"))
      (node (ref "USBC1") (pin "B4") (pinfunction "VBUS_B4") (pintype "passive"))
      (node (ref "USBC1") (pin "B9") (pinfunction "VBUS_B9") (pintype "passive"))
    )
    (net (code "7") (name "CC1") (class "Default")
      (node (ref "D5") (pin "4") (pinfunction "D2+_4") (pintype "passive"))
      (node (ref "D5") (pin "7") (pinfunction "NC_7") (pintype "passive"))
      (node (ref "U2") (pin "2") (pinfunction "CC1_2") (pintype "bidirectional"))
      (node (ref "USBC1") (pin "A5") (pinfunction "CC1_A5") (pintype "passive"))
    )
    (net (code "8") (name "CC2") (class "Default")
      (node (ref "D5") (pin "5") (pinfunction "D2-_5") (pintype "passive"))
      (node (ref "D5") (pin "6") (pinfunction "NC_6") (pintype "passive"))
      (node (ref "U2") (pin "1") (pinfunction "CC2_1") (pintype "bidirectional"))
      (node (ref "USBC1") (pin "B5") (pinfunction "CC2_B5") (pintype "passive"))
    )
    (net (code "9") (name "CLK-2") (class "Default")
      (node (ref "R24") (pin "1") (pinfunction "1_1") (pintype "passive"))
      (node (ref "U3") (pin "29") (pinfunction "S2CK_M2D0_29") (pintype "bidirectional"))
    )
    (net (code "10") (name "CMD-2") (class "Default")
      (node (ref "H1") (pin "M5") (pinfunction "CMD_M5") (pintype "bidirectional"))
      (node (ref "U3") (pin "30") (pinfunction "S2CM_M2D2_30") (pintype "bidirectional"))
    )
    (net (code "11") (name "CRX1_N") (class "Default")
      (node (ref "D1") (pin "2") (pinfunction "D1-_2") (pintype "passive"))
      (node (ref "D1") (pin "9") (pinfunction "NC_9") (pintype "passive"))
      (node (ref "U2") (pin "15") (pinfunction "RX1P_15") (pintype "bidirectional"))
      (node (ref "USBC1") (pin "B10") (pinfunction "SSRXN1_B10") (pintype "passive"))
    )
    (net (code "12") (name "CRX1_P") (class "Default")
      (node (ref "D1") (pin "1") (pinfunction "D1+_1") (pintype "passive"))
      (node (ref "D1") (pin "10") (pinfunction "NC_10") (pintype "passive"))
      (node (ref "U2") (pin "14") (pinfunction "RX1N_14") (pintype "bidirectional"))
      (node (ref "USBC1") (pin "B11") (pinfunction "SSRXP1_B11") (pintype "passive"))
    )
    (net (code "13") (name "CRX2_N") (class "Default")
      (node (ref "D2") (pin "1") (pinfunction "D1+_1") (pintype "passive"))
      (node (ref "D2") (pin "10") (pinfunction "NC_10") (pintype "passive"))
      (node (ref "U2") (pin "18") (pinfunction "RX2N_18") (pintype "bidirectional"))
      (node (ref "USBC1") (pin "A10") (pinfunction "SSRXN2_A10") (pintype "passive"))
    )
    (net (code "14") (name "CRX2_P") (class "Default")
      (node (ref "D2") (pin "2") (pinfunction "D1-_2") (pintype "passive"))
      (node (ref "D2") (pin "9") (pinfunction "NC_9") (pintype "passive"))
      (node (ref "U2") (pin "19") (pinfunction "RX2P_19") (pintype "bidirectional"))
      (node (ref "USBC1") (pin "A11") (pinfunction "SSRXP2_A11") (pintype "passive"))
    )
    (net (code "15") (name "CSBU1") (class "Default")
      (node (ref "USBC1") (pin "A8") (pinfunction "SBU1_A8") (pintype "passive"))
    )
    (net (code "16") (name "CSBU2") (class "Default")
      (node (ref "USBC1") (pin "B8") (pinfunction "SBU2_B8") (pintype "passive"))
    )
    (net (code "17") (name "CTX1_N") (class "Default")
      (node (ref "C5") (pin "1") (pinfunction "1_1") (pintype "passive"))
      (node (ref "D1") (pin "5") (pinfunction "D2-_5") (pintype "passive"))
      (node (ref "D1") (pin "6") (pinfunction "NC_6") (pintype "passive"))
      (node (ref "USBC1") (pin "A3") (pinfunction "SSTXN1_A3") (pintype "passive"))
    )
    (net (code "18") (name "CTX1_P") (class "Default")
      (node (ref "C6") (pin "1") (pinfunction "1_1") (pintype "passive"))
      (node (ref "D1") (pin "4") (pinfunction "D2+_4") (pintype "passive"))
      (node (ref "D1") (pin "7") (pinfunction "NC_7") (pintype "passive"))
      (node (ref "USBC1") (pin "A2") (pinfunction "SSTXP1_A2") (pintype "passive"))
    )
    (net (code "19") (name "CTX2_N") (class "Default")
      (node (ref "C7") (pin "1") (pinfunction "1_1") (pintype "passive"))
      (node (ref "D2") (pin "4") (pinfunction "D2+_4") (pintype "passive"))
      (node (ref "D2") (pin "7") (pinfunction "NC_7") (pintype "passive"))
      (node (ref "USBC1") (pin "B3") (pinfunction "SSTXN2_B3") (pintype "passive"))
    )
    (net (code "20") (name "CTX2_P") (class "Default")
      (node (ref "C8") (pin "1") (pinfunction "1_1") (pintype "passive"))
      (node (ref "D2") (pin "5") (pinfunction "D2-_5") (pintype "passive"))
      (node (ref "D2") (pin "6") (pinfunction "NC_6") (pintype "passive"))
      (node (ref "USBC1") (pin "B2") (pinfunction "SSTXP2_B2") (pintype "passive"))
    )
    (net (code "21") (name "DAT0-1") (class "Default")
      (node (ref "H1") (pin "B3") (pinfunction "DAT4_B3") (pintype "bidirectional"))
      (node (ref "U3") (pin "38") (pinfunction "S1D0_M1D1_38") (pintype "bidirectional"))
    )
    (net (code "22") (name "DAT0-2") (class "Default")
      (node (ref "H1") (pin "A3") (pinfunction "DAT0_A3") (pintype "bidirectional"))
      (node (ref "U3") (pin "28") (pinfunction "S2D0_M2D1_28") (pintype "bidirectional"))
    )
    (net (code "23") (name "DAT1-1") (class "Default")
      (node (ref "H1") (pin "B4") (pinfunction "DAT5_B4") (pintype "bidirectional"))
      (node (ref "U3") (pin "37") (pinfunction "S1D1_M1BS_37") (pintype "bidirectional"))
    )
    (net (code "24") (name "DAT1-2") (class "Default")
      (node (ref "H1") (pin "A4") (pinfunction "DAT1_A4") (pintype "bidirectional"))
      (node (ref "U3") (pin "27") (pinfunction "S2D1_M2BS_27") (pintype "bidirectional"))
    )
    (net (code "25") (name "DAT2-1") (class "Default")
      (node (ref "H1") (pin "B5") (pinfunction "DAT6_B5") (pintype "bidirectional"))
      (node (ref "U3") (pin "42") (pinfunction "S1D2_M1CK_42") (pintype "bidirectional"))
    )
    (net (code "26") (name "DAT2-2") (class "Default")
      (node (ref "H1") (pin "A5") (pinfunction "DAT2_A5") (pintype "bidirectional"))
      (node (ref "U3") (pin "32") (pinfunction "S2D2_M2CK_32") (pintype "bidirectional"))
    )
    (net (code "27") (name "DAT3-1") (class "Default")
      (node (ref "H1") (pin "B6") (pinfunction "DAT7_B6") (pintype "bidirectional"))
      (node (ref "U3") (pin "41") (pinfunction "S1D3_M1D3_41") (pintype "bidirectional"))
    )
    (net (code "28") (name "DAT3-2") (class "Default")
      (node (ref "H1") (pin "B2") (pinfunction "DAT3_B2") (pintype "bidirectional"))
      (node (ref "U3") (pin "31") (pinfunction "S2D3_M2D3_31") (pintype "bidirectional"))
    )
    (net (code "29") (name "DIR") (class "Default")
      (node (ref "R16") (pin "1") (pinfunction "1_1") (pintype "passive"))
      (node (ref "U2") (pin "11") (pinfunction "DIR_11") (pintype "open_collector"))
    )
    (net (code "30") (name "DS1RX_N") (class "Default")
      (node (ref "C41") (pin "1") (pinfunction "1_1") (pintype "passive"))
      (node (ref "IC1") (pin "15") (pinfunction "RXP_DS1_15") (pintype "bidirectional"))
    )
    (net (code "31") (name "DS1RX_P") (class "Default")
      (node (ref "C42") (pin "1") (pinfunction "1_1") (pintype "passive"))
      (node (ref "IC1") (pin "14") (pinfunction "RXN_DS1_14") (pintype "bidirectional"))
    )
    (net (code "32") (name "DS1TXE_N") (class "Default")
      (node (ref "C48") (pin "2") (pinfunction "2_2") (pintype "passive"))
      (node (ref "IC1") (pin "13") (pinfunction "TXP_DS1_13") (pintype "bidirectional"))
    )
    (net (code "33") (name "DS1TXE_P") (class "Default")
      (node (ref "C43") (pin "2") (pinfunction "2_2") (pintype "passive"))
      (node (ref "IC1") (pin "12") (pinfunction "TXN_DS1_12") (pintype "bidirectional"))
    )
    (net (code "34") (name "DS1TX_N") (class "Default")
      (node (ref "C48") (pin "1") (pinfunction "1_1") (pintype "passive"))
      (node (ref "U3") (pin "10") (pinfunction "RXN_10") (pintype "bidirectional"))
    )
    (net (code "35") (name "DS1TX_P") (class "Default")
      (node (ref "C43") (pin "1") (pinfunction "1_1") (pintype "passive"))
      (node (ref "U3") (pin "11") (pinfunction "RXP_11") (pintype "bidirectional"))
    )
    (net (code "36") (name "DS1_RX_N") (class "Default")
      (node (ref "C41") (pin "2") (pinfunction "2_2") (pintype "passive"))
      (node (ref "U3") (pin "7") (pinfunction "TXN_7") (pintype "bidirectional"))
    )
    (net (code "37") (name "DS1_RX_P") (class "Default")
      (node (ref "C42") (pin "2") (pinfunction "2_2") (pintype "passive"))
      (node (ref "U3") (pin "8") (pinfunction "TXP_8") (pintype "bidirectional"))
    )
    (net (code "38") (name "DS1_USB2_N") (class "Default")
      (node (ref "IC1") (pin "43") (pinfunction "DM1_43") (pintype "bidirectional"))
      (node (ref "R28") (pin "1") (pinfunction "1_1") (pintype "passive"))
    )
    (net (code "39") (name "DS1_USB2_P") (class "Default")
      (node (ref "IC1") (pin "44") (pinfunction "DP1_44") (pintype "bidirectional"))
      (node (ref "R29") (pin "1") (pinfunction "1_1") (pintype "passive"))
    )
    (net (code "40") (name "DS2_USB2_N") (class "Default")
      (node (ref "IC1") (pin "46") (pinfunction "DM2_46") (pintype "bidirectional"))
      (node (ref "J3") (pin "4") (pinfunction "4_4") (pintype "bidirectional"))
    )
    (net (code "41") (name "DS2_USB2_P") (class "Default")
      (node (ref "IC1") (pin "47") (pinfunction "DP2_47") (pintype "bidirectional"))
      (node (ref "J3") (pin "5") (pinfunction "5_5") (pintype "bidirectional"))
    )
    (net (code "42") (name "DS3RX_N") (class "Default")
      (node (ref "IC1") (pin "26") (pinfunction "RXN_DS3_26") (pintype "bidirectional"))
      (node (ref "J9") (pin "10") (pinfunction "10_10") (pintype "bidirectional"))
    )
    (net (code "43") (name "DS3RX_P") (class "Default")
      (node (ref "IC1") (pin "27") (pinfunction "RXP_DS3_27") (pintype "bidirectional"))
      (node (ref "J9") (pin "11") (pinfunction "11_11") (pintype "bidirectional"))
    )
    (net (code "44") (name "DS3TXE_N") (class "Default")
      (node (ref "C3") (pin "2") (pinfunction "2_2") (pintype "passive"))
      (node (ref "J9") (pin "7") (pinfunction "7_7") (pintype "bidirectional"))
    )
    (net (code "45") (name "DS3TXE_P") (class "Default")
      (node (ref "C4") (pin "2") (pinfunction "2_2") (pintype "passive"))
      (node (ref "J9") (pin "8") (pinfunction "8_8") (pintype "bidirectional"))
    )
    (net (code "46") (name "DS3TX_N") (class "Default")
      (node (ref "C3") (pin "1") (pinfunction "1_1") (pintype "passive"))
      (node (ref "IC1") (pin "24") (pinfunction "TXN_DS3_24") (pintype "bidirectional"))
    )
    (net (code "47") (name "DS3TX_P") (class "Default")
      (node (ref "C4") (pin "1") (pinfunction "1_1") (pintype "passive"))
      (node (ref "IC1") (pin "25") (pinfunction "TXP_DS3_25") (pintype "bidirectional"))
    )
    (net (code "48") (name "DS3_USB2_N") (class "Default")
      (node (ref "IC1") (pin "49") (pinfunction "DM3_49") (pintype "bidirectional"))
      (node (ref "J9") (pin "4") (pinfunction "4_4") (pintype "bidirectional"))
    )
    (net (code "49") (name "DS3_USB2_P") (class "Default")
      (node (ref "IC1") (pin "50") (pinfunction "DP3_50") (pintype "bidirectional"))
      (node (ref "J9") (pin "5") (pinfunction "5_5") (pintype "bidirectional"))
    )
    (net (code "50") (name "DS4_USB2_N") (class "Default")
      (node (ref "IC1") (pin "52") (pinfunction "DM4_52") (pintype "bidirectional"))
      (node (ref "J1") (pin "4") (pinfunction "4_4") (pintype "bidirectional"))
    )
    (net (code "51") (name "DS4_USB2_P") (class "Default")
      (node (ref "IC1") (pin "53") (pinfunction "DP4_53") (pintype "bidirectional"))
      (node (ref "J1") (pin "3") (pinfunction "3_3") (pintype "bidirectional"))
    )
    (net (code "52") (name "DVDD12") (class "Default")
      (node (ref "C75") (pin "2") (pinfunction "2_2") (pintype "passive"))
      (node (ref "C83") (pin "2") (pinfunction "2_2") (pintype "passive"))
      (node (ref "U3") (pin "26") (pinfunction "DVDD12_26") (pintype "bidirectional"))
      (node (ref "U3") (pin "9") (pinfunction "AVDD12_9") (pintype "bidirectional"))
    )
    (net (code "53") (name "DVDD33") (class "Default")
      (node (ref "C50") (pin "2") (pinfunction "2_2") (pintype "passive"))
      (node (ref "C73") (pin "2") (pinfunction "2_2") (pintype "passive"))
      (node (ref "C78") (pin "2") (pinfunction "2_2") (pintype "passive"))
      (node (ref "C79") (pin "2") (pinfunction "2_2") (pintype "passive"))
      (node (ref "C80") (pin "2") (pinfunction "2_2") (pintype "passive"))
      (node (ref "C99") (pin "2") (pinfunction "2_2") (pintype "passive"))
      (node (ref "H1") (pin "E6") (pinfunction "VCC_1_E6") (pintype "bidirectional"))
      (node (ref "H1") (pin "F5") (pinfunction "VCC_2_F5") (pintype "bidirectional"))
      (node (ref "H1") (pin "J10") (pinfunction "VCC_3_J10") (pintype "bidirectional"))
      (node (ref "H1") (pin "K9") (pinfunction "VCC_4_K9") (pintype "bidirectional"))
      (node (ref "U3") (pin "15") (pinfunction "AVDD33_15") (pintype "bidirectional"))
      (node (ref "U3") (pin "23") (pinfunction "S1M1_VCC_23") (pintype "bidirectional"))
      (node (ref "U3") (pin "25") (pinfunction "DVDD33_25") (pintype "bidirectional"))
      (node (ref "U3") (pin "34") (pinfunction "DVDD33_34") (pintype "bidirectional"))
      (node (ref "U3") (pin "44") (pinfunction "DVDD33_44") (pintype "bidirectional"))
      (node (ref "U3") (pin "6") (pinfunction "AVDD33_6") (pintype "bidirectional"))
    )
    (net (code "54") (name "D_N") (class "Default")
      (node (ref "IC2") (pin "3") (pinfunction "D-_3") (pintype "bidirectional"))
      (node (ref "R28") (pin "2") (pinfunction "2_2") (pintype "passive"))
    )
    (net (code "55") (name "D_P") (class "Default")
      (node (ref "IC2") (pin "4") (pinfunction "D+_4") (pintype "bidirectional"))
      (node (ref "R29") (pin "2") (pinfunction "2_2") (pintype "passive"))
    )
    (net (code "56") (name "D_UP_N") (class "Default")
      (node (ref "D5") (pin "1") (pinfunction "D1+_1") (pintype "passive"))
      (node (ref "D5") (pin "10") (pinfunction "NC_10") (pintype "passive"))
      (node (ref "IC1") (pin "41") (pinfunction "DM0_41") (pintype "bidirectional"))
      (node (ref "USBC1") (pin "A7") (pinfunction "DN1_A7") (pintype "passive"))
      (node (ref "USBC1") (pin "B7") (pinfunction "DN2_B7") (pintype "passive"))
    )
    (net (code "57") (name "D_UP_P") (class "Default")
      (node (ref "D5") (pin "2") (pinfunction "D1-_2") (pintype "passive"))
      (node (ref "D5") (pin "9") (pinfunction "NC_9") (pintype "passive"))
      (node (ref "IC1") (pin "42") (pinfunction "DP0_42") (pintype "bidirectional"))
      (node (ref "USBC1") (pin "A6") (pinfunction "DP1_A6") (pintype "passive"))
      (node (ref "USBC1") (pin "B6") (pinfunction "DP2_B6") (pintype "passive"))
    )
    (net (code "58") (name "EMMC_RST-2") (class "Default")
      (node (ref "C71") (pin "2") (pinfunction "2_2") (pintype "passive"))
      (node (ref "H1") (pin "K5") (pinfunction "RST__N_K5") (pintype "bidirectional"))
      (node (ref "R25") (pin "2") (pinfunction "2_2") (pintype "passive"))
      (node (ref "U3") (pin "36") (pinfunction "SD2_CDZ_36") (pintype "bidirectional"))
    )
    (net (code "59") (name "EN1") (class "Default")
      (node (ref "IC2") (pin "28") (pinfunction "PB4_(PCINT4/ADC11)_28") (pintype "bidirectional"))
      (node (ref "R38") (pin "1") (pinfunction "1_1") (pintype "passive"))
      (node (ref "U6") (pin "4") (pinfunction "EN/~{EN}_4") (pintype "bidirectional"))
    )
    (net (code "60") (name "EN2") (class "Default")
      (node (ref "IC2") (pin "26") (pinfunction "PD6_(T1/~{OC4D}/ADC9)_26") (pintype "bidirectional"))
      (node (ref "R41") (pin "2") (pinfunction "2_2") (pintype "passive"))
      (node (ref "U7") (pin "4") (pinfunction "EN/~{EN}_4") (pintype "bidirectional"))
    )
    (net (code "61") (name "EN3") (class "Default")
      (node (ref "IC2") (pin "31") (pinfunction "PC6_(OC3A/~{OC4A})_31") (pintype "bidirectional"))
      (node (ref "R35") (pin "2") (pinfunction "2_2") (pintype "passive"))
      (node (ref "U8") (pin "4") (pinfunction "EN/~{EN}_4") (pintype "bidirectional"))
    )
    (net (code "62") (name "FAN_PWM") (class "Default")
      (node (ref "IC2") (pin "30") (pinfunction "PB6_(PCINT6/OC1B/OC4B/ADC13)_30") (pintype "bidirectional"))
      (node (ref "Q2") (pin "1") (pinfunction "INPUT_1") (pintype "passive"))
    )
    (net (code "63") (name "GND") (class "Default")
      (node (ref "C1") (pin "2") (pinfunction "2_2") (pintype "passive"))
      (node (ref "C10") (pin "1") (pinfunction "1_1") (pintype "passive"))
      (node (ref "C100") (pin "1") (pinfunction "1_1") (pintype "passive"))
      (node (ref "C101") (pin "2") (pinfunction "2_2") (pintype "passive"))
      (node (ref "C102") (pin "2") (pinfunction "2_2") (pintype "passive"))
      (node (ref "C103") (pin "2") (pinfunction "2_2") (pintype "passive"))
      (node (ref "C12") (pin "1") (pinfunction "1_1") (pintype "passive"))
      (node (ref "C13") (pin "1") (pinfunction "1_1") (pintype "passive"))
      (node (ref "C14") (pin "1") (pinfunction "1_1") (pintype "passive"))
      (node (ref "C17") (pin "2") (pinfunction "2_2") (pintype "passive"))
      (node (ref "C18") (pin "1") (pinfunction "1_1") (pintype "passive"))
      (node (ref "C19") (pin "2") (pinfunction "2_2") (pintype "passive"))
      (node (ref "C2") (pin "1") (pinfunction "1_1") (pintype "passive"))
      (node (ref "C20") (pin "1") (pinfunction "1_1") (pintype "passive"))
      (node (ref "C21") (pin "2") (pinfunction "2_2") (pintype "passive"))
      (node (ref "C22") (pin "2") (pinfunction "2_2") (pintype "passive"))
      (node (ref "C23") (pin "1") (pinfunction "1_1") (pintype "passive"))
      (node (ref "C24") (pin "2") (pinfunction "2_2") (pintype "passive"))
      (node (ref "C25") (pin "2") (pinfunction "2_2") (pintype "passive"))
      (node (ref "C26") (pin "1") (pinfunction "1_1") (pintype "passive"))
      (node (ref "C27") (pin "1") (pinfunction "1_1") (pintype "passive"))
      (node (ref "C28") (pin "1") (pinfunction "1_1") (pintype "passive"))
      (node (ref "C29") (pin "2") (pinfunction "2_2") (pintype "passive"))
      (node (ref "C30") (pin "2") (pinfunction "2_2") (pintype "passive"))
      (node (ref "C31") (pin "2") (pinfunction "2_2") (pintype "passive"))
      (node (ref "C32") (pin "1") (pinfunction "1_1") (pintype "passive"))
      (node (ref "C33") (pin "2") (pinfunction "2_2") (pintype "passive"))
      (node (ref "C34") (pin "2") (pinfunction "2_2") (pintype "passive"))
      (node (ref "C35") (pin "2") (pinfunction "2_2") (pintype "passive"))
      (node (ref "C36") (pin "2") (pinfunction "2_2") (pintype "passive"))
      (node (ref "C37") (pin "2") (pinfunction "2_2") (pintype "passive"))
      (node (ref "C38") (pin "1") (pinfunction "1_1") (pintype "passive"))
      (node (ref "C39") (pin "1") (pinfunction "1_1") (pintype "passive"))
      (node (ref "C40") (pin "1") (pinfunction "1_1") (pintype "passive"))
      (node (ref "C44") (pin "2") (pinfunction "2_2") (pintype "passive"))
      (node (ref "C45") (pin "1") (pinfunction "1_1") (pintype "passive"))
      (node (ref "C46") (pin "1") (pinfunction "1_1") (pintype "passive"))
      (node (ref "C47") (pin "1") (pinfunction "1_1") (pintype "passive"))
      (node (ref "C49") (pin "2") (pinfunction "2_2") (pintype "passive"))
      (node (ref "C50") (pin "1") (pinfunction "1_1") (pintype "passive"))
      (node (ref "C51") (pin "1") (pinfunction "1_1") (pintype "passive"))
      (node (ref "C52") (pin "2") (pinfunction "2_2") (pintype "passive"))
      (node (ref "C53") (pin "1") (pinfunction "1_1") (pintype "passive"))
      (node (ref "C54") (pin "1") (pinfunction "1_1") (pintype "passive"))
      (node (ref "C55") (pin "1") (pinfunction "1_1") (pintype "passive"))
      (node (ref "C56") (pin "1") (pinfunction "1_1") (pintype "passive"))
      (node (ref "C57") (pin "1") (pinfunction "1_1") (pintype "passive"))
      (node (ref "C59") (pin "2") (pinfunction "2_2") (pintype "passive"))
      (node (ref "C60") (pin "2") (pinfunction "2_2") (pintype "passive"))
      (node (ref "C61") (pin "2") (pinfunction "2_2") (pintype "passive"))
      (node (ref "C62") (pin "1") (pinfunction "1_1") (pintype "passive"))
      (node (ref "C63") (pin "2") (pinfunction "2_2") (pintype "passive"))
      (node (ref "C64") (pin "2") (pinfunction "2_2") (pintype "passive"))
      (node (ref "C65") (pin "2") (pinfunction "2_2") (pintype "passive"))
      (node (ref "C66") (pin "1") (pinfunction "1_1") (pintype "passive"))
      (node (ref "C67") (pin "2") (pinfunction "2_2") (pintype "passive"))
      (node (ref "C68") (pin "2") (pinfunction "2_2") (pintype "passive"))
      (node (ref "C71") (pin "1") (pinfunction "1_1") (pintype "passive"))
      (node (ref "C72") (pin "1") (pinfunction "1_1") (pintype "passive"))
      (node (ref "C73") (pin "1") (pinfunction "1_1") (pintype "passive"))
      (node (ref "C74") (pin "1") (pinfunction "1_1") (pintype "passive"))
      (node (ref "C75") (pin "1") (pinfunction "1_1") (pintype "passive"))
      (node (ref "C76") (pin "2") (pinfunction "2_2") (pintype "passive"))
      (node (ref "C77") (pin "2") (pinfunction "2_2") (pintype "passive"))
      (node (ref "C78") (pin "1") (pinfunction "1_1") (pintype "passive"))
      (node (ref "C79") (pin "1") (pinfunction "1_1") (pintype "passive"))
      (node (ref "C80") (pin "1") (pinfunction "1_1") (pintype "passive"))
      (node (ref "C81") (pin "1") (pinfunction "1_1") (pintype "passive"))
      (node (ref "C82") (pin "1") (pinfunction "1_1") (pintype "passive"))
      (node (ref "C83") (pin "1") (pinfunction "1_1") (pintype "passive"))
      (node (ref "C84") (pin "1") (pinfunction "1_1") (pintype "passive"))
      (node (ref "C85") (pin "2") (pinfunction "2_2") (pintype "passive"))
      (node (ref "C86") (pin "1") (pinfunction "1_1") (pintype "passive"))
      (node (ref "C87") (pin "1") (pinfunction "1_1") (pintype "passive"))
      (node (ref "C88") (pin "2") (pinfunction "2_2") (pintype "passive"))
      (node (ref "C89") (pin "2") (pinfunction "2_2") (pintype "passive"))
      (node (ref "C9") (pin "1") (pinfunction "1_1") (pintype "passive"))
      (node (ref "C90") (pin "2") (pinfunction "2_2") (pintype "passive"))
      (node (ref "C91") (pin "2") (pinfunction "2_2") (pintype "passive"))
      (node (ref "C92") (pin "2") (pinfunction "2_2") (pintype "passive"))
      (node (ref "C93") (pin "2") (pinfunction "2_2") (pintype "passive"))
      (node (ref "C94") (pin "2") (pinfunction "2_2") (pintype "passive"))
      (node (ref "C95") (pin "2") (pinfunction "2_2") (pintype "passive"))
      (node (ref "C96") (pin "1") (pinfunction "1_1") (pintype "passive"))
      (node (ref "C97") (pin "1") (pinfunction "1_1") (pintype "passive"))
      (node (ref "C98") (pin "1") (pinfunction "1_1") (pintype "passive"))
      (node (ref "C99") (pin "1") (pinfunction "1_1") (pintype "passive"))
      (node (ref "D1") (pin "3") (pinfunction "GND_3") (pintype "passive"))
      (node (ref "D1") (pin "8") (pinfunction "GND_8") (pintype "passive"))
      (node (ref "D2") (pin "3") (pinfunction "GND_3") (pintype "passive"))
      (node (ref "D2") (pin "8") (pinfunction "GND_8") (pintype "passive"))
      (node (ref "D3") (pin "2") (pinfunction "-_2") (pintype "passive"))
      (node (ref "D4") (pin "+") (pinfunction "+_+") (pintype "passive"))
      (node (ref "D5") (pin "3") (pinfunction "GND_3") (pintype "passive"))
      (node (ref "D5") (pin "8") (pinfunction "GND_8") (pintype "passive"))
      (node (ref "D6") (pin "2") (pinfunction "-_2") (pintype "passive"))
      (node (ref "D7") (pin "+") (pinfunction "A_+") (pintype "passive"))
      (node (ref "H1") (pin "A6") (pinfunction "VSS_1_A6") (pintype "bidirectional"))
      (node (ref "H1") (pin "C4") (pinfunction "VSSQ_1_C4") (pintype "bidirectional"))
      (node (ref "H1") (pin "E7") (pinfunction "VSS_2_E7") (pintype "bidirectional"))
      (node (ref "H1") (pin "G5") (pinfunction "VSS_3_G5") (pintype "bidirectional"))
      (node (ref "H1") (pin "H10") (pinfunction "VSS_4_H10") (pintype "bidirectional"))
      (node (ref "H1") (pin "J5") (pinfunction "VSS_5_J5") (pintype "bidirectional"))
      (node (ref "H1") (pin "K8") (pinfunction "VSS_6_K8") (pintype "bidirectional"))
      (node (ref "H1") (pin "N2") (pinfunction "VSSQ_2_N2") (pintype "bidirectional"))
      (node (ref "H1") (pin "N5") (pinfunction "VSSQ_3_N5") (pintype "bidirectional"))
      (node (ref "H1") (pin "P4") (pinfunction "VSSQ_4_P4") (pintype "bidirectional"))
      (node (ref "H1") (pin "P6") (pinfunction "VSSQ_5_P6") (pintype "bidirectional"))
      (node (ref "IC1") (pin "65") (pinfunction "EP_65") (pintype "bidirectional"))
      (node (ref "IC2") (pin "15") (pinfunction "GND_1_15") (pintype "bidirectional"))
      (node (ref "IC2") (pin "23") (pinfunction "GND_2_23") (pintype "bidirectional"))
      (node (ref "IC2") (pin "35") (pinfunction "GND_3_35") (pintype "bidirectional"))
      (node (ref "IC2") (pin "43") (pinfunction "GND_4_43") (pintype "bidirectional"))
      (node (ref "IC2") (pin "45") (pinfunction "GND_5_45") (pintype "bidirectional"))
      (node (ref "IC2") (pin "5") (pinfunction "UGND_5") (pintype "bidirectional"))
      (node (ref "J1") (pin "1") (pinfunction "1_1") (pintype "bidirectional"))
      (node (ref "J1") (pin "2") (pinfunction "2_2") (pintype "bidirectional"))
      (node (ref "J10") (pin "4") (pinfunction "4_4") (pintype "bidirectional"))
      (node (ref "J3") (pin "12") (pinfunction "12_12") (pintype "bidirectional"))
      (node (ref "J3") (pin "3") (pinfunction "3_3") (pintype "bidirectional"))
      (node (ref "J3") (pin "6") (pinfunction "6_6") (pintype "bidirectional"))
      (node (ref "J3") (pin "9") (pinfunction "9_9") (pintype "bidirectional"))
      (node (ref "J4") (pin "1") (pinfunction "1_1") (pintype "bidirectional"))
      (node (ref "J5") (pin "1") (pinfunction "S_1") (pintype "passive"))
      (node (ref "J6") (pin "1") (pinfunction "S_1") (pintype "passive"))
      (node (ref "J9") (pin "12") (pinfunction "12_12") (pintype "bidirectional"))
      (node (ref "J9") (pin "3") (pinfunction "3_3") (pintype "bidirectional"))
      (node (ref "J9") (pin "6") (pinfunction "6_6") (pintype "bidirectional"))
      (node (ref "J9") (pin "9") (pinfunction "9_9") (pintype "bidirectional"))
      (node (ref "K1") (pin "2") (pinfunction "2_2") (pintype "bidirectional"))
      (node (ref "Q2") (pin "2") (pinfunction "E_2") (pintype "passive"))
      (node (ref "R13") (pin "2") (pinfunction "2_2") (pintype "passive"))
      (node (ref "R2") (pin "2") (pinfunction "2_2") (pintype "passive"))
      (node (ref "R21") (pin "1") (pinfunction "1_1") (pintype "passive"))
      (node (ref "R22") (pin "1") (pinfunction "1_1") (pintype "passive"))
      (node (ref "R39") (pin "1") (pinfunction "1_1") (pintype "passive"))
      (node (ref "R4") (pin "1") (pinfunction "1_1") (pintype "passive"))
      (node (ref "R9") (pin "2") (pinfunction "2_2") (pintype "passive"))
      (node (ref "U1") (pin "4") (pinfunction "GND_4") (pintype "bidirectional"))
      (node (ref "U2") (pin "12") (pinfunction "EN_MUX_N_12") (pintype "input"))
      (node (ref "U2") (pin "13") (pinfunction "GND_2_13") (pintype "power_in"))
      (node (ref "U2") (pin "28") (pinfunction "GND_28") (pintype "power_in"))
      (node (ref "U2") (pin "29") (pinfunction "EN_CC_N_29") (pintype "input"))
      (node (ref "U2") (pin "31") (pinfunction "PAD_31") (pintype "power_in"))
      (node (ref "U2") (pin "4") (pinfunction "PORT_4") (pintype "input"))
      (node (ref "U3") (pin "12") (pinfunction "GND_12") (pintype "bidirectional"))
      (node (ref "U3") (pin "3") (pinfunction "GND_3") (pintype "bidirectional"))
      (node (ref "U3") (pin "35") (pinfunction "MS2_INS/SD2_WP_35") (pintype "bidirectional"))
      (node (ref "U3") (pin "THERMAL") (pinfunction "THERMAL_THERMAL") (pintype "bidirectional"))
      (node (ref "U4") (pin "2") (pinfunction "GND_2") (pintype "bidirectional"))
      (node (ref "U5") (pin "2") (pinfunction "GND_2") (pintype "bidirectional"))
      (node (ref "U6") (pin "2") (pinfunction "GND_2") (pintype "bidirectional"))
      (node (ref "U7") (pin "2") (pinfunction "GND_2") (pintype "bidirectional"))
      (node (ref "U8") (pin "2") (pinfunction "GND_2") (pintype "bidirectional"))
      (node (ref "USBC1") (pin "0") (pinfunction "0_0") (pintype "passive"))
      (node (ref "USBC1") (pin "0-1") (pinfunction "0_0-1") (pintype "passive"))
      (node (ref "USBC1") (pin "0-2") (pinfunction "0_0-2") (pintype "passive"))
      (node (ref "USBC1") (pin "0-3") (pinfunction "0_0-3") (pintype "passive"))
      (node (ref "USBC1") (pin "0-4") (pinfunction "0_0-4") (pintype "passive"))
      (node (ref "USBC1") (pin "0-5") (pinfunction "0_0-5") (pintype "passive"))
      (node (ref "USBC1") (pin "0-6") (pinfunction "0_0-6") (pintype "passive"))
      (node (ref "USBC1") (pin "0-7") (pinfunction "0_0-7") (pintype "passive"))
      (node (ref "USBC1") (pin "0-8") (pinfunction "0_0-8") (pintype "passive"))
      (node (ref "USBC1") (pin "0-9") (pinfunction "0_0-9") (pintype "passive"))
      (node (ref "USBC1") (pin "1") (pinfunction "0_1") (pintype "passive"))
      (node (ref "USBC1") (pin "2") (pinfunction "0_2") (pintype "passive"))
      (node (ref "USBC1") (pin "A1") (pinfunction "GND_A1") (pintype "passive"))
      (node (ref "USBC1") (pin "A12") (pinfunction "GND_A12") (pintype "passive"))
      (node (ref "USBC1") (pin "B1") (pinfunction "GND_B1") (pintype "passive"))
      (node (ref "USBC1") (pin "B12") (pinfunction "GND_B12") (pintype "passive"))
      (node (ref "X1") (pin "1") (pinfunction "1NC_1") (pintype "bidirectional"))
      (node (ref "X1") (pin "3") (pinfunction "3NC_3") (pintype "bidirectional"))
      (node (ref "X3") (pin "1") (pinfunction "1NC_1") (pintype "bidirectional"))
      (node (ref "X3") (pin "3") (pinfunction "3NC_3") (pintype "bidirectional"))
      (node (ref "X4") (pin "1") (pinfunction "1NC_1") (pintype "bidirectional"))
      (node (ref "X4") (pin "3") (pinfunction "3NC_3") (pintype "bidirectional"))
    )
    (net (code "64") (name "INT") (class "Default")
      (node (ref "IC2") (pin "1") (pinfunction "(INT.6/AIN0)_PE6_1") (pintype "bidirectional"))
      (node (ref "J2") (pin "P$1") (pinfunction "1_P$1") (pintype "bidirectional"))
    )
    (net (code "65") (name "LED") (class "Default")
      (node (ref "IC2") (pin "32") (pinfunction "PC7_(ICP3/CLK0/OC4A)_32") (pintype "bidirectional"))
      (node (ref "R32") (pin "1") (pinfunction "1_1") (pintype "passive"))
    )
    (net (code "66") (name "MISO") (class "Default")
      (node (ref "IC2") (pin "11") (pinfunction "(PDO/PCINT3/MISO)_PB3_11") (pintype "bidirectional"))
      (node (ref "J10") (pin "1") (pinfunction "1_1") (pintype "bidirectional"))
    )
    (net (code "67") (name "MOSI") (class "Default")
      (node (ref "IC2") (pin "10") (pinfunction "(PDI/PCINT2/MOSI)_PB2_10") (pintype "bidirectional"))
      (node (ref "J10") (pin "5") (pinfunction "5_5") (pintype "bidirectional"))
    )
    (net (code "68") (name "Net-(C87-Pad2)") (class "Default")
      (node (ref "C87") (pin "2") (pinfunction "2_2") (pintype "passive"))
      (node (ref "R37") (pin "1") (pinfunction "1_1") (pintype "passive"))
      (node (ref "R38") (pin "2") (pinfunction "2_2") (pintype "passive"))
    )
    (net (code "69") (name "Net-(C98-Pad2)") (class "Default")
      (node (ref "C98") (pin "2") (pinfunction "2_2") (pintype "passive"))
      (node (ref "R41") (pin "1") (pinfunction "1_1") (pintype "passive"))
      (node (ref "R7") (pin "2") (pinfunction "2_2") (pintype "passive"))
    )
    (net (code "70") (name "Net-(D3-+)") (class "Default")
      (node (ref "D3") (pin "1") (pinfunction "+_1") (pintype "passive"))
      (node (ref "R23") (pin "2") (pinfunction "2_2") (pintype "passive"))
    )
    (net (code "71") (name "Net-(D6-+)") (class "Default")
      (node (ref "D6") (pin "1") (pinfunction "+_1") (pintype "passive"))
      (node (ref "R32") (pin "2") (pinfunction "2_2") (pintype "passive"))
    )
    (net (code "72") (name "Net-(D7-C)") (class "Default")
      (node (ref "C100") (pin "2") (pinfunction "2_2") (pintype "passive"))
      (node (ref "D7") (pin "-") (pinfunction "C_-") (pintype "passive"))
      (node (ref "J5") (pin "2") (pinfunction "S_2") (pintype "passive"))
      (node (ref "Q1") (pin "3") (pinfunction "D_3") (pintype "passive"))
    )
    (net (code "73") (name "Net-(H1-CLK)") (class "Default")
      (node (ref "H1") (pin "M6") (pinfunction "CLK_M6") (pintype "bidirectional"))
      (node (ref "R24") (pin "2") (pinfunction "2_2") (pintype "passive"))
    )
    (net (code "74") (name "Net-(H1-VDDI)") (class "Default")
      (node (ref "C72") (pin "2") (pinfunction "2_2") (pintype "passive"))
      (node (ref "H1") (pin "C2") (pinfunction "VDDI_C2") (pintype "bidirectional"))
    )
    (net (code "75") (name "Net-(IC1-PSELF)") (class "Default")
      (node (ref "IC1") (pin "60") (pinfunction "PSELF_60") (pintype "bidirectional"))
      (node (ref "R8") (pin "1") (pinfunction "1_1") (pintype "passive"))
    )
    (net (code "76") (name "Net-(IC1-RTERM)") (class "Default")
      (node (ref "IC1") (pin "1") (pinfunction "RTERM_1") (pintype "bidirectional"))
      (node (ref "R4") (pin "2") (pinfunction "2_2") (pintype "passive"))
    )
    (net (code "77") (name "Net-(IC1-VBUS)") (class "Default")
      (node (ref "C2") (pin "2") (pinfunction "2_2") (pintype "passive"))
      (node (ref "IC1") (pin "38") (pinfunction "VBUS_38") (pintype "bidirectional"))
      (node (ref "R34") (pin "1") (pinfunction "1_1") (pintype "passive"))
      (node (ref "R39") (pin "2") (pinfunction "2_2") (pintype "passive"))
    )
    (net (code "78") (name "Net-(IC1-X1)") (class "Default")
      (node (ref "C1") (pin "1") (pinfunction "1_1") (pintype "passive"))
      (node (ref "IC1") (pin "3") (pinfunction "X1_3") (pintype "bidirectional"))
      (node (ref "R3") (pin "1") (pinfunction "1_1") (pintype "passive"))
      (node (ref "X4") (pin "4") (pinfunction "4_4") (pintype "bidirectional"))
    )
    (net (code "79") (name "Net-(IC1-X2)") (class "Default")
      (node (ref "C21") (pin "1") (pinfunction "1_1") (pintype "passive"))
      (node (ref "IC1") (pin "4") (pinfunction "X2_4") (pintype "bidirectional"))
      (node (ref "R3") (pin "2") (pinfunction "2_2") (pintype "passive"))
      (node (ref "X4") (pin "2") (pinfunction "2_2") (pintype "bidirectional"))
    )
    (net (code "80") (name "Net-(IC2-UCAP)") (class "Default")
      (node (ref "C30") (pin "1") (pinfunction "1_1") (pintype "passive"))
      (node (ref "IC2") (pin "6") (pinfunction "UCAP_6") (pintype "bidirectional"))
    )
    (net (code "81") (name "Net-(K1-Pad1)") (class "Default")
      (node (ref "K1") (pin "1") (pinfunction "1_1") (pintype "bidirectional"))
      (node (ref "R31") (pin "2") (pinfunction "2_2") (pintype "passive"))
    )
    (net (code "82") (name "Net-(Q1-G)") (class "Default")
      (node (ref "Q1") (pin "1") (pinfunction "G_1") (pintype "passive"))
      (node (ref "Q2") (pin "3") (pinfunction "C_3") (pintype "passive"))
      (node (ref "R36") (pin "1") (pinfunction "1_1") (pintype "passive"))
    )
    (net (code "83") (name "Net-(U1-~{HOLD}{slash}IO3)") (class "Default")
      (node (ref "R11") (pin "1") (pinfunction "1_1") (pintype "passive"))
      (node (ref "U1") (pin "7") (pinfunction "~{HOLD}/IO3_7") (pintype "bidirectional"))
    )
    (net (code "84") (name "Net-(U1-~{WP}{slash}IO2)") (class "Default")
      (node (ref "R10") (pin "2") (pinfunction "2_2") (pintype "passive"))
      (node (ref "U1") (pin "3") (pinfunction "~{WP}/IO2_3") (pintype "bidirectional"))
    )
    (net (code "85") (name "Net-(U2-VBUS_DET)") (class "Default")
      (node (ref "R20") (pin "1") (pinfunction "1_1") (pintype "passive"))
      (node (ref "U2") (pin "5") (pinfunction "VBUS_DET_5") (pintype "input"))
    )
    (net (code "86") (name "Net-(U3-LED)") (class "Default")
      (node (ref "R23") (pin "1") (pinfunction "1_1") (pintype "passive"))
      (node (ref "U3") (pin "21") (pinfunction "LED_21") (pintype "bidirectional"))
    )
    (net (code "87") (name "Net-(U3-RTERM)") (class "Default")
      (node (ref "R22") (pin "2") (pinfunction "2_2") (pintype "passive"))
      (node (ref "U3") (pin "16") (pinfunction "RTERM_16") (pintype "bidirectional"))
    )
    (net (code "88") (name "Net-(U3-SD1_CDZ)") (class "Default")
      (node (ref "R21") (pin "2") (pinfunction "2_2") (pintype "passive"))
      (node (ref "U3") (pin "1") (pinfunction "SD1_CDZ_1") (pintype "bidirectional"))
    )
    (net (code "89") (name "Net-(U4-FB)") (class "Default")
      (node (ref "C11") (pin "1") (pinfunction "1_1") (pintype "passive"))
      (node (ref "R6") (pin "2") (pinfunction "2_2") (pintype "passive"))
      (node (ref "R9") (pin "1") (pinfunction "1_1") (pintype "passive"))
      (node (ref "U4") (pin "5") (pinfunction "FB_5") (pintype "bidirectional"))
    )
    (net (code "90") (name "Net-(U4-LX)") (class "Default")
      (node (ref "L1") (pin "1") (pinfunction "1_1") (pintype "passive"))
      (node (ref "U4") (pin "3") (pinfunction "LX_3") (pintype "bidirectional"))
    )
    (net (code "91") (name "Net-(U5-FB)") (class "Default")
      (node (ref "C58") (pin "1") (pinfunction "1_1") (pintype "passive"))
      (node (ref "R12") (pin "2") (pinfunction "2_2") (pintype "passive"))
      (node (ref "R13") (pin "1") (pinfunction "1_1") (pintype "passive"))
      (node (ref "U5") (pin "5") (pinfunction "FB_5") (pintype "bidirectional"))
    )
    (net (code "92") (name "Net-(U5-LX)") (class "Default")
      (node (ref "L10") (pin "1") (pinfunction "1_1") (pintype "passive"))
      (node (ref "U5") (pin "3") (pinfunction "LX_3") (pintype "bidirectional"))
    )
    (net (code "93") (name "Net-(U6-OUT)") (class "Default")
      (node (ref "C26") (pin "2") (pinfunction "2_2") (pintype "passive"))
      (node (ref "C27") (pin "2") (pinfunction "2_2") (pintype "passive"))
      (node (ref "C28") (pin "2") (pinfunction "2_2") (pintype "passive"))
      (node (ref "L2") (pin "1") (pinfunction "1_1") (pintype "passive"))
      (node (ref "U6") (pin "1") (pinfunction "OUT_1") (pintype "bidirectional"))
    )
    (net (code "94") (name "Net-(U7-OUT)") (class "Default")
      (node (ref "C32") (pin "2") (pinfunction "2_2") (pintype "passive"))
      (node (ref "C38") (pin "2") (pinfunction "2_2") (pintype "passive"))
      (node (ref "C39") (pin "2") (pinfunction "2_2") (pintype "passive"))
      (node (ref "L4") (pin "1") (pinfunction "1_1") (pintype "passive"))
      (node (ref "U7") (pin "1") (pinfunction "OUT_1") (pintype "bidirectional"))
    )
    (net (code "95") (name "Net-(U8-OUT)") (class "Default")
      (node (ref "C53") (pin "2") (pinfunction "2_2") (pintype "passive"))
      (node (ref "C54") (pin "2") (pinfunction "2_2") (pintype "passive"))
      (node (ref "C55") (pin "2") (pinfunction "2_2") (pintype "passive"))
      (node (ref "L9") (pin "1") (pinfunction "1_1") (pintype "passive"))
      (node (ref "U8") (pin "1") (pinfunction "OUT_1") (pintype "bidirectional"))
    )
    (net (code "96") (name "OUT1") (class "Default")
      (node (ref "R18") (pin "1") (pinfunction "1_1") (pintype "passive"))
      (node (ref "U2") (pin "25") (pinfunction "SDA_OUT1_25") (pintype "bidirectional"))
    )
    (net (code "97") (name "OUT2") (class "Default")
      (node (ref "R19") (pin "1") (pinfunction "1_1") (pintype "passive"))
      (node (ref "U2") (pin "26") (pinfunction "SCL_OUT2_26") (pintype "bidirectional"))
    )
    (net (code "98") (name "PGANG") (class "Default")
      (node (ref "IC1") (pin "55") (pinfunction "PGANG_55") (pintype "bidirectional"))
      (node (ref "R14") (pin "1") (pinfunction "1_1") (pintype "passive"))
    )
    (net (code "99") (name "RESET") (class "Default")
      (node (ref "C95") (pin "1") (pinfunction "1_1") (pintype "passive"))
      (node (ref "IC2") (pin "13") (pinfunction "~{RESET}_13") (pintype "bidirectional"))
      (node (ref "J10") (pin "3") (pinfunction "3_3") (pintype "bidirectional"))
      (node (ref "R30") (pin "1") (pinfunction "1_1") (pintype "passive"))
      (node (ref "R31") (pin "1") (pinfunction "1_1") (pintype "passive"))
    )
    (net (code "100") (name "RESETJ") (class "Default")
      (node (ref "C25") (pin "1") (pinfunction "1_1") (pintype "passive"))
      (node (ref "IC1") (pin "61") (pinfunction "RESETJ_61") (pintype "bidirectional"))
      (node (ref "R1") (pin "2") (pinfunction "2_2") (pintype "passive"))
      (node (ref "R2") (pin "1") (pinfunction "1_1") (pintype "passive"))
    )
    (net (code "101") (name "RX_UP_N") (class "Default")
      (node (ref "IC1") (pin "8") (pinfunction "RXN_UP_8") (pintype "bidirectional"))
      (node (ref "U2") (pin "10") (pinfunction "RXN_10") (pintype "bidirectional"))
    )
    (net (code "102") (name "RX_UP_P") (class "Default")
      (node (ref "IC1") (pin "9") (pinfunction "RXP_UP_9") (pintype "bidirectional"))
      (node (ref "U2") (pin "9") (pinfunction "RXP_9") (pintype "bidirectional"))
    )
    (net (code "103") (name "SCK") (class "Default")
      (node (ref "IC2") (pin "9") (pinfunction "(PCINT1/SCLK)_PB1_9") (pintype "bidirectional"))
      (node (ref "J10") (pin "2") (pinfunction "2_2") (pintype "bidirectional"))
    )
    (net (code "104") (name "SCL") (class "Default")
      (node (ref "IC2") (pin "18") (pinfunction "(OC0B/SCL/INT0)_PD0_18") (pintype "bidirectional"))
      (node (ref "J6") (pin "4") (pinfunction "S_4") (pintype "passive"))
      (node (ref "R15") (pin "2") (pinfunction "2_2") (pintype "passive"))
    )
    (net (code "105") (name "SDA") (class "Default")
      (node (ref "IC2") (pin "19") (pinfunction "(SDA/INT1)_PD1_19") (pintype "bidirectional"))
      (node (ref "J6") (pin "3") (pinfunction "S_3") (pintype "passive"))
      (node (ref "R27") (pin "2") (pinfunction "2_2") (pintype "passive"))
    )
    (net (code "106") (name "SPI_CK") (class "Default")
      (node (ref "IC1") (pin "35") (pinfunction "P_SPI_CK_35") (pintype "bidirectional"))
      (node (ref "U1") (pin "6") (pinfunction "CLK_6") (pintype "bidirectional"))
    )
    (net (code "107") (name "SPI_CZ") (class "Default")
      (node (ref "IC1") (pin "36") (pinfunction "P_SPI_CZ_36") (pintype "bidirectional"))
      (node (ref "U1") (pin "1") (pinfunction "~{CS}_1") (pintype "bidirectional"))
    )
    (net (code "108") (name "SPI_DI") (class "Default")
      (node (ref "IC1") (pin "59") (pinfunction "P_SPI_DI_59") (pintype "bidirectional"))
      (node (ref "U1") (pin "2") (pinfunction "DO/IO1_2") (pintype "bidirectional"))
    )
    (net (code "109") (name "SPI_DO") (class "Default")
      (node (ref "IC1") (pin "58") (pinfunction "P_SPI_DO_58") (pintype "bidirectional"))
      (node (ref "U1") (pin "5") (pinfunction "DI/IO0_5") (pintype "bidirectional"))
    )
    (net (code "110") (name "TX1_N") (class "Default")
      (node (ref "C5") (pin "2") (pinfunction "2_2") (pintype "passive"))
      (node (ref "U2") (pin "17") (pinfunction "TX1P_17") (pintype "bidirectional"))
    )
    (net (code "111") (name "TX1_P") (class "Default")
      (node (ref "C6") (pin "2") (pinfunction "2_2") (pintype "passive"))
      (node (ref "U2") (pin "16") (pinfunction "TX1N_16") (pintype "bidirectional"))
    )
    (net (code "112") (name "TX2_N") (class "Default")
      (node (ref "C7") (pin "2") (pinfunction "2_2") (pintype "passive"))
      (node (ref "U2") (pin "20") (pinfunction "TX2N_20") (pintype "bidirectional"))
    )
    (net (code "113") (name "TX2_P") (class "Default")
      (node (ref "C8") (pin "2") (pinfunction "2_2") (pintype "passive"))
      (node (ref "U2") (pin "21") (pinfunction "TX2P_21") (pintype "bidirectional"))
    )
    (net (code "114") (name "TXUP_N") (class "Default")
      (node (ref "C69") (pin "2") (pinfunction "2_2") (pintype "passive"))
      (node (ref "IC1") (pin "6") (pinfunction "TXN_UP_6") (pintype "bidirectional"))
    )
    (net (code "115") (name "TXUP_P") (class "Default")
      (node (ref "C70") (pin "2") (pinfunction "2_2") (pintype "passive"))
      (node (ref "IC1") (pin "7") (pinfunction "TXP_UP_7") (pintype "bidirectional"))
    )
    (net (code "116") (name "TX_N") (class "Default")
      (node (ref "C69") (pin "1") (pinfunction "1_1") (pintype "passive"))
      (node (ref "U2") (pin "7") (pinfunction "TXN_7") (pintype "bidirectional"))
    )
    (net (code "117") (name "TX_P") (class "Default")
      (node (ref "C70") (pin "1") (pinfunction "1_1") (pintype "passive"))
      (node (ref "U2") (pin "6") (pinfunction "TXP_6") (pintype "bidirectional"))
    )
    (net (code "118") (name "USB3TX_N") (class "Default")
      (node (ref "C16") (pin "2") (pinfunction "2_2") (pintype "passive"))
      (node (ref "J3") (pin "7") (pinfunction "7_7") (pintype "bidirectional"))
    )
    (net (code "119") (name "USB3TX_P") (class "Default")
      (node (ref "C15") (pin "2") (pinfunction "2_2") (pintype "passive"))
      (node (ref "J3") (pin "8") (pinfunction "8_8") (pintype "bidirectional"))
    )
    (net (code "120") (name "USB3_DS2RX_N") (class "Default")
      (node (ref "IC1") (pin "20") (pinfunction "RXN_DS2_20") (pintype "bidirectional"))
      (node (ref "J3") (pin "10") (pinfunction "10_10") (pintype "bidirectional"))
    )
    (net (code "121") (name "USB3_DS2RX_P") (class "Default")
      (node (ref "IC1") (pin "21") (pinfunction "RXP_DS2_21") (pintype "bidirectional"))
      (node (ref "J3") (pin "11") (pinfunction "11_11") (pintype "bidirectional"))
    )
    (net (code "122") (name "USB3_DS2TXE_N") (class "Default")
      (node (ref "C16") (pin "1") (pinfunction "1_1") (pintype "passive"))
      (node (ref "IC1") (pin "18") (pinfunction "TXN_DS2_18") (pintype "bidirectional"))
    )
    (net (code "123") (name "USB3_DS2TXE_P") (class "Default")
      (node (ref "C15") (pin "1") (pinfunction "1_1") (pintype "passive"))
      (node (ref "IC1") (pin "19") (pinfunction "TXP_DS2_19") (pintype "bidirectional"))
    )
    (net (code "124") (name "VBUS") (class "Default")
      (node (ref "C10") (pin "2") (pinfunction "2_2") (pintype "passive"))
      (node (ref "C101") (pin "1") (pinfunction "1_1") (pintype "passive"))
      (node (ref "C18") (pin "2") (pinfunction "2_2") (pintype "passive"))
      (node (ref "C20") (pin "2") (pinfunction "2_2") (pintype "passive"))
      (node (ref "C23") (pin "2") (pinfunction "2_2") (pintype "passive"))
      (node (ref "C29") (pin "1") (pinfunction "1_1") (pintype "passive"))
      (node (ref "C45") (pin "2") (pinfunction "2_2") (pintype "passive"))
      (node (ref "C46") (pin "2") (pinfunction "2_2") (pintype "passive"))
      (node (ref "C47") (pin "2") (pinfunction "2_2") (pintype "passive"))
      (node (ref "C56") (pin "2") (pinfunction "2_2") (pintype "passive"))
      (node (ref "C57") (pin "2") (pinfunction "2_2") (pintype "passive"))
      (node (ref "C86") (pin "2") (pinfunction "2_2") (pintype "passive"))
      (node (ref "C9") (pin "2") (pinfunction "2_2") (pintype "passive"))
      (node (ref "C96") (pin "2") (pinfunction "2_2") (pintype "passive"))
      (node (ref "C97") (pin "2") (pinfunction "2_2") (pintype "passive"))
      (node (ref "L3") (pin "1") (pinfunction "1_1") (pintype "passive"))
      (node (ref "L7") (pin "1") (pinfunction "1_1") (pintype "passive"))
      (node (ref "L8") (pin "1") (pinfunction "1_1") (pintype "passive"))
      (node (ref "Q1") (pin "2") (pinfunction "S_2") (pintype "passive"))
      (node (ref "R1") (pin "1") (pinfunction "1_1") (pintype "passive"))
      (node (ref "R18") (pin "2") (pinfunction "2_2") (pintype "passive"))
      (node (ref "R19") (pin "2") (pinfunction "2_2") (pintype "passive"))
      (node (ref "R20") (pin "2") (pinfunction "2_2") (pintype "passive"))
      (node (ref "R34") (pin "2") (pinfunction "2_2") (pintype "passive"))
      (node (ref "R36") (pin "2") (pinfunction "2_2") (pintype "passive"))
      (node (ref "R5") (pin "2") (pinfunction "2_2") (pintype "passive"))
      (node (ref "U2") (pin "30") (pinfunction "VDD5_30") (pintype "power_in"))
      (node (ref "U4") (pin "1") (pinfunction "EN_1") (pintype "bidirectional"))
      (node (ref "U4") (pin "4") (pinfunction "IN_4") (pintype "bidirectional"))
      (node (ref "U5") (pin "1") (pinfunction "EN_1") (pintype "bidirectional"))
      (node (ref "U5") (pin "4") (pinfunction "IN_4") (pintype "bidirectional"))
      (node (ref "U6") (pin "5") (pinfunction "IN_5") (pintype "bidirectional"))
      (node (ref "U7") (pin "5") (pinfunction "IN_5") (pintype "bidirectional"))
      (node (ref "U8") (pin "5") (pinfunction "IN_5") (pintype "bidirectional"))
    )
    (net (code "125") (name "VBUS1") (class "Default")
      (node (ref "C19") (pin "1") (pinfunction "1_1") (pintype "passive"))
      (node (ref "J9") (pin "1") (pinfunction "1_1") (pintype "bidirectional"))
      (node (ref "J9") (pin "2") (pinfunction "2_2") (pintype "bidirectional"))
      (node (ref "L4") (pin "2") (pinfunction "2_2") (pintype "passive"))
    )
    (net (code "126") (name "VBUS2") (class "Default")
      (node (ref "C24") (pin "1") (pinfunction "1_1") (pintype "passive"))
      (node (ref "J3") (pin "1") (pinfunction "1_1") (pintype "bidirectional"))
      (node (ref "J3") (pin "2") (pinfunction "2_2") (pintype "bidirectional"))
      (node (ref "L2") (pin "2") (pinfunction "2_2") (pintype "passive"))
    )
    (net (code "127") (name "VBUS3") (class "Default")
      (node (ref "C40") (pin "2") (pinfunction "2_2") (pintype "passive"))
      (node (ref "C52") (pin "1") (pinfunction "1_1") (pintype "passive"))
      (node (ref "L9") (pin "2") (pinfunction "2_2") (pintype "passive"))
      (node (ref "U3") (pin "22") (pinfunction "VBUS_22") (pintype "bidirectional"))
    )
    (net (code "128") (name "VBUS4") (class "Default")
      (node (ref "C22") (pin "1") (pinfunction "1_1") (pintype "passive"))
      (node (ref "J1") (pin "5") (pinfunction "5_5") (pintype "bidirectional"))
      (node (ref "J1") (pin "6") (pinfunction "6_6") (pintype "bidirectional"))
      (node (ref "L7") (pin "2") (pinfunction "2_2") (pintype "passive"))
    )
    (net (code "129") (name "VBUS5") (class "Default")
      (node (ref "C44") (pin "1") (pinfunction "1_1") (pintype "passive"))
      (node (ref "J4") (pin "2") (pinfunction "2_2") (pintype "bidirectional"))
      (node (ref "L8") (pin "2") (pinfunction "2_2") (pintype "passive"))
    )
    (net (code "130") (name "VBUS6") (class "Default")
      (node (ref "C17") (pin "1") (pinfunction "1_1") (pintype "passive"))
      (node (ref "C89") (pin "1") (pinfunction "1_1") (pintype "passive"))
      (node (ref "C90") (pin "1") (pinfunction "1_1") (pintype "passive"))
      (node (ref "IC2") (pin "2") (pinfunction "UVCC_2") (pintype "bidirectional"))
      (node (ref "IC2") (pin "7") (pinfunction "VBUS_7") (pintype "bidirectional"))
      (node (ref "L3") (pin "2") (pinfunction "2_2") (pintype "passive"))
    )
    (net (code "131") (name "VCCQ") (class "Default")
      (node (ref "C74") (pin "2") (pinfunction "2_2") (pintype "passive"))
      (node (ref "C81") (pin "2") (pinfunction "2_2") (pintype "passive"))
      (node (ref "C82") (pin "2") (pinfunction "2_2") (pintype "passive"))
      (node (ref "H1") (pin "C6") (pinfunction "VCCQ_1_C6") (pintype "bidirectional"))
      (node (ref "H1") (pin "M4") (pinfunction "VCCQ_2_M4") (pintype "bidirectional"))
      (node (ref "H1") (pin "P3") (pinfunction "VCCQ_3_P3") (pintype "bidirectional"))
      (node (ref "H1") (pin "P5") (pinfunction "VCCQ_4_P5") (pintype "bidirectional"))
      (node (ref "R25") (pin "1") (pinfunction "1_1") (pintype "passive"))
      (node (ref "U3") (pin "33") (pinfunction "VUHS_2_33") (pintype "bidirectional"))
      (node (ref "U3") (pin "43") (pinfunction "VUHS_1_43") (pintype "bidirectional"))
    )
    (net (code "132") (name "X1") (class "Default")
      (node (ref "C77") (pin "1") (pinfunction "1_1") (pintype "passive"))
      (node (ref "R26") (pin "2") (pinfunction "2_2") (pintype "passive"))
      (node (ref "U3") (pin "13") (pinfunction "X1_13") (pintype "bidirectional"))
      (node (ref "X3") (pin "2") (pinfunction "2_2") (pintype "bidirectional"))
    )
    (net (code "133") (name "X2") (class "Default")
      (node (ref "C76") (pin "1") (pinfunction "1_1") (pintype "passive"))
      (node (ref "R26") (pin "1") (pinfunction "1_1") (pintype "passive"))
      (node (ref "U3") (pin "14") (pinfunction "X2_14") (pintype "bidirectional"))
      (node (ref "X3") (pin "4") (pinfunction "4_4") (pintype "bidirectional"))
    )
    (net (code "134") (name "XTAL1") (class "Default")
      (node (ref "C31") (pin "1") (pinfunction "1_1") (pintype "passive"))
      (node (ref "IC2") (pin "17") (pinfunction "XTAL1_17") (pintype "bidirectional"))
      (node (ref "X1") (pin "2") (pinfunction "2_2") (pintype "bidirectional"))
    )
    (net (code "135") (name "XTAL2") (class "Default")
      (node (ref "C85") (pin "1") (pinfunction "1_1") (pintype "passive"))
      (node (ref "IC2") (pin "16") (pinfunction "XTAL2_16") (pintype "bidirectional"))
      (node (ref "X1") (pin "4") (pinfunction "4_4") (pintype "bidirectional"))
    )
    (net (code "136") (name "unconnected-(H1-DS-PadH5)") (class "Default")
      (node (ref "H1") (pin "H5") (pinfunction "DS_H5") (pintype "bidirectional"))
    )
    (net (code "137") (name "unconnected-(IC1-OVCUR1J-Pad57)") (class "Default")
      (node (ref "IC1") (pin "57") (pinfunction "OVCUR1J_57") (pintype "bidirectional"))
    )
    (net (code "138") (name "unconnected-(IC1-PWREN1J-Pad37)") (class "Default")
      (node (ref "IC1") (pin "37") (pinfunction "PWREN1J_37") (pintype "bidirectional"))
    )
    (net (code "139") (name "unconnected-(IC1-RXN_DS4-Pad32)") (class "Default")
      (node (ref "IC1") (pin "32") (pinfunction "RXN_DS4_32") (pintype "bidirectional"))
    )
    (net (code "140") (name "unconnected-(IC1-RXP_DS4-Pad33)") (class "Default")
      (node (ref "IC1") (pin "33") (pinfunction "RXP_DS4_33") (pintype "bidirectional"))
    )
    (net (code "141") (name "unconnected-(IC1-TXN_DS4-Pad30)") (class "Default")
      (node (ref "IC1") (pin "30") (pinfunction "TXN_DS4_30") (pintype "bidirectional"))
    )
    (net (code "142") (name "unconnected-(IC1-TXP_DS4-Pad31)") (class "Default")
      (node (ref "IC1") (pin "31") (pinfunction "TXP_DS4_31") (pintype "bidirectional"))
    )
    (net (code "143") (name "unconnected-(IC1-V5-Pad64)") (class "Default")
      (node (ref "IC1") (pin "64") (pinfunction "V5_64") (pintype "bidirectional"))
    )
    (net (code "144") (name "unconnected-(IC1-VP12_1-Pad5)") (class "Default")
      (node (ref "IC1") (pin "5") (pinfunction "VP12_1_5") (pintype "bidirectional"))
    )
    (net (code "145") (name "unconnected-(IC1-VP12_3-Pad11)") (class "Default")
      (node (ref "IC1") (pin "11") (pinfunction "VP12_3_11") (pintype "bidirectional"))
    )
    (net (code "146") (name "unconnected-(IC1-VP12_5-Pad17)") (class "Default")
      (node (ref "IC1") (pin "17") (pinfunction "VP12_5_17") (pintype "bidirectional"))
    )
    (net (code "147") (name "unconnected-(IC1-VP12_7-Pad23)") (class "Default")
      (node (ref "IC1") (pin "23") (pinfunction "VP12_7_23") (pintype "bidirectional"))
    )
    (net (code "148") (name "unconnected-(IC1-VP12_9-Pad29)") (class "Default")
      (node (ref "IC1") (pin "29") (pinfunction "VP12_9_29") (pintype "bidirectional"))
    )
    (net (code "149") (name "unconnected-(IC1-VP33CR-Pad2)") (class "Default")
      (node (ref "IC1") (pin "2") (pinfunction "VP33CR_2") (pintype "bidirectional"))
    )
    (net (code "150") (name "unconnected-(IC2-(PCINT7{slash}OC0A{slash}OC1C{slash}~{RTS})_PB7-Pad12)") (class "Default")
      (node (ref "IC2") (pin "12") (pinfunction "(PCINT7/OC0A/OC1C/~{RTS})_PB7_12") (pintype "bidirectional"))
    )
    (net (code "151") (name "unconnected-(IC2-(RXD1{slash}INT2)_PD2-Pad20)") (class "Default")
      (node (ref "IC2") (pin "20") (pinfunction "(RXD1/INT2)_PD2_20") (pintype "bidirectional"))
    )
    (net (code "152") (name "unconnected-(IC2-(SS{slash}PCINT0)_PB0-Pad8)") (class "Default")
      (node (ref "IC2") (pin "8") (pinfunction "(SS/PCINT0)_PB0_8") (pintype "bidirectional"))
    )
    (net (code "153") (name "unconnected-(IC2-(TXD1{slash}INT3)_PD3-Pad21)") (class "Default")
      (node (ref "IC2") (pin "21") (pinfunction "(TXD1/INT3)_PD3_21") (pintype "bidirectional"))
    )
    (net (code "154") (name "unconnected-(IC2-(XCK1{slash}~{CTS})_PD5-Pad22)") (class "Default")
      (node (ref "IC2") (pin "22") (pinfunction "(XCK1/~{CTS})_PD5_22") (pintype "bidirectional"))
    )
    (net (code "155") (name "unconnected-(IC2-PB5_(PCINT5{slash}OC1A{slash}~{OC4B}{slash}ADC12)-Pad29)") (class "Default")
      (node (ref "IC2") (pin "29") (pinfunction "PB5_(PCINT5/OC1A/~{OC4B}/ADC12)_29") (pintype "bidirectional"))
    )
    (net (code "156") (name "unconnected-(IC2-PE2_(H~{WB})-Pad33)") (class "Default")
      (node (ref "IC2") (pin "33") (pinfunction "PE2_(H~{WB})_33") (pintype "bidirectional"))
    )
    (net (code "157") (name "unconnected-(IC2-PF0_(ADC0)-Pad41)") (class "Default")
      (node (ref "IC2") (pin "41") (pinfunction "PF0_(ADC0)_41") (pintype "bidirectional"))
    )
    (net (code "158") (name "unconnected-(IC2-PF1_(ADC1)-Pad40)") (class "Default")
      (node (ref "IC2") (pin "40") (pinfunction "PF1_(ADC1)_40") (pintype "bidirectional"))
    )
    (net (code "159") (name "unconnected-(IC2-PF4_(ADC4{slash}TCK)-Pad39)") (class "Default")
      (node (ref "IC2") (pin "39") (pinfunction "PF4_(ADC4/TCK)_39") (pintype "bidirectional"))
    )
    (net (code "160") (name "unconnected-(IC2-PF5_(ADC5{slash}TMS)-Pad38)") (class "Default")
      (node (ref "IC2") (pin "38") (pinfunction "PF5_(ADC5/TMS)_38") (pintype "bidirectional"))
    )
    (net (code "161") (name "unconnected-(IC2-PF6_(ADC6{slash}TDO)-Pad37)") (class "Default")
      (node (ref "IC2") (pin "37") (pinfunction "PF6_(ADC6/TDO)_37") (pintype "bidirectional"))
    )
    (net (code "162") (name "unconnected-(J1-G1-PadMH1)") (class "Default")
      (node (ref "J1") (pin "MH1") (pinfunction "G1_MH1") (pintype "bidirectional"))
    )
    (net (code "163") (name "unconnected-(J1-G2-PadMH2)") (class "Default")
      (node (ref "J1") (pin "MH2") (pinfunction "G2_MH2") (pintype "bidirectional"))
    )
    (net (code "164") (name "unconnected-(J3-G1-PadP$13)") (class "Default")
      (node (ref "J3") (pin "P$13") (pinfunction "G1_P$13") (pintype "bidirectional"))
    )
    (net (code "165") (name "unconnected-(J3-G2-PadP$14)") (class "Default")
      (node (ref "J3") (pin "P$14") (pinfunction "G2_P$14") (pintype "bidirectional"))
    )
    (net (code "166") (name "unconnected-(J9-G1-PadP$13)") (class "Default")
      (node (ref "J9") (pin "P$13") (pinfunction "G1_P$13") (pintype "bidirectional"))
    )
    (net (code "167") (name "unconnected-(J9-G2-PadP$14)") (class "Default")
      (node (ref "J9") (pin "P$14") (pinfunction "G2_P$14") (pintype "bidirectional"))
    )
    (net (code "168") (name "unconnected-(U2-ADDR-Pad22)") (class "Default")
      (node (ref "U2") (pin "22") (pinfunction "ADDR_22") (pintype "input"))
    )
    (net (code "169") (name "unconnected-(U2-CURRENT_MODE-Pad3)") (class "Default")
      (node (ref "U2") (pin "3") (pinfunction "CURRENT_MODE_3") (pintype "input"))
    )
    (net (code "170") (name "unconnected-(U2-ID-Pad27)") (class "Default")
      (node (ref "U2") (pin "27") (pinfunction "ID_27") (pintype "open_collector"))
    )
    (net (code "171") (name "unconnected-(U2-INT_OUT3_N-Pad23)") (class "Default")
      (node (ref "U2") (pin "23") (pinfunction "INT_OUT3_N_23") (pintype "open_collector"))
    )
    (net (code "172") (name "unconnected-(U2-VCONN_FAULT_N-Pad24)") (class "Default")
      (node (ref "U2") (pin "24") (pinfunction "VCONN_FAULT_N_24") (pintype "open_collector"))
    )
    (net (code "173") (name "unconnected-(U3-DM-Pad4)") (class "Default")
      (node (ref "U3") (pin "4") (pinfunction "DM_4") (pintype "bidirectional"))
    )
    (net (code "174") (name "unconnected-(U3-DP-Pad5)") (class "Default")
      (node (ref "U3") (pin "5") (pinfunction "DP_5") (pintype "bidirectional"))
    )
    (net (code "175") (name "unconnected-(U3-MS1_INS{slash}SD1_WP-Pad2)") (class "Default")
      (node (ref "U3") (pin "2") (pinfunction "MS1_INS/SD1_WP_2") (pintype "bidirectional"))
    )
    (net (code "176") (name "unconnected-(U3-S1CK_M1D0-Pad39)") (class "Default")
      (node (ref "U3") (pin "39") (pinfunction "S1CK_M1D0_39") (pintype "bidirectional"))
    )
    (net (code "177") (name "unconnected-(U3-S1CM_M1D2-Pad40)") (class "Default")
      (node (ref "U3") (pin "40") (pinfunction "S1CM_M1D2_40") (pintype "bidirectional"))
    )
    (net (code "178") (name "unconnected-(U3-S1D4_M1D7-Pad48)") (class "Default")
      (node (ref "U3") (pin "48") (pinfunction "S1D4_M1D7_48") (pintype "bidirectional"))
    )
    (net (code "179") (name "unconnected-(U3-S1D5_M1D6-Pad47)") (class "Default")
      (node (ref "U3") (pin "47") (pinfunction "S1D5_M1D6_47") (pintype "bidirectional"))
    )
    (net (code "180") (name "unconnected-(U3-S1D6_M1D5-Pad46)") (class "Default")
      (node (ref "U3") (pin "46") (pinfunction "S1D6_M1D5_46") (pintype "bidirectional"))
    )
    (net (code "181") (name "unconnected-(U3-S1D7_M1D4-Pad45)") (class "Default")
      (node (ref "U3") (pin "45") (pinfunction "S1D7_M1D4_45") (pintype "bidirectional"))
    )
    (net (code "182") (name "unconnected-(U3-S2M2_VCC-Pad24)") (class "Default")
      (node (ref "U3") (pin "24") (pinfunction "S2M2_VCC_24") (pintype "bidirectional"))
    )
    (net (code "183") (name "unconnected-(U3-SPI_CLK-Pad19)") (class "Default")
      (node (ref "U3") (pin "19") (pinfunction "SPI_CLK_19") (pintype "bidirectional"))
    )
    (net (code "184") (name "unconnected-(U3-SPI_CS-Pad20)") (class "Default")
      (node (ref "U3") (pin "20") (pinfunction "SPI_CS_20") (pintype "bidirectional"))
    )
    (net (code "185") (name "unconnected-(U3-SPI_MISO-Pad17)") (class "Default")
      (node (ref "U3") (pin "17") (pinfunction "SPI_MISO_17") (pintype "bidirectional"))
    )
    (net (code "186") (name "unconnected-(U3-SPI_MOSI-Pad18)") (class "Default")
      (node (ref "U3") (pin "18") (pinfunction "SPI_MOSI_18") (pintype "bidirectional"))
    )
    (net (code "187") (name "~{FLT1}") (class "Default")
      (node (ref "IC2") (pin "27") (pinfunction "PD7_(T0/OC4D/ADC10)_27") (pintype "bidirectional"))
      (node (ref "R33") (pin "2") (pinfunction "2_2") (pintype "passive"))
      (node (ref "U6") (pin "3") (pinfunction "~{FLT}_3") (pintype "bidirectional"))
    )
    (net (code "188") (name "~{FLT2}") (class "Default")
      (node (ref "IC2") (pin "25") (pinfunction "PD4_(ICP1/ADC8)_25") (pintype "bidirectional"))
      (node (ref "R40") (pin "2") (pinfunction "2_2") (pintype "passive"))
      (node (ref "U7") (pin "3") (pinfunction "~{FLT}_3") (pintype "bidirectional"))
    )
    (net (code "189") (name "~{FLT3}") (class "Default")
      (node (ref "IC2") (pin "36") (pinfunction "PF7_(ADC7/TDI)_36") (pintype "bidirectional"))
      (node (ref "R17") (pin "2") (pinfunction "2_2") (pintype "passive"))
      (node (ref "U8") (pin "3") (pinfunction "~{FLT}_3") (pintype "bidirectional"))
    )
  )
)
